# SCH_Reserach-project_2025-06-22.net
KiCad netlist of a schematic drawn in EasyEDA
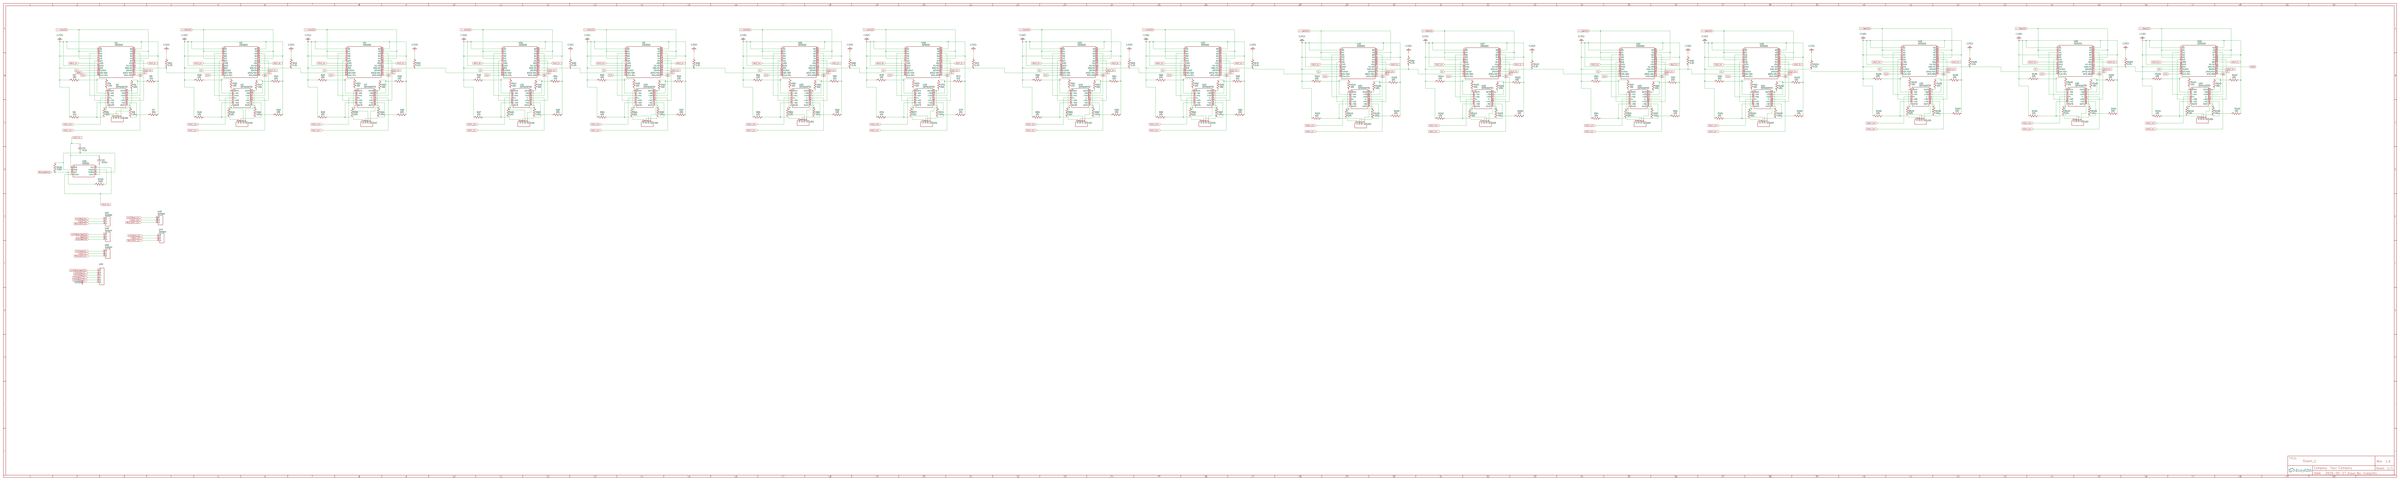
[diagram p0: Sheet_1]
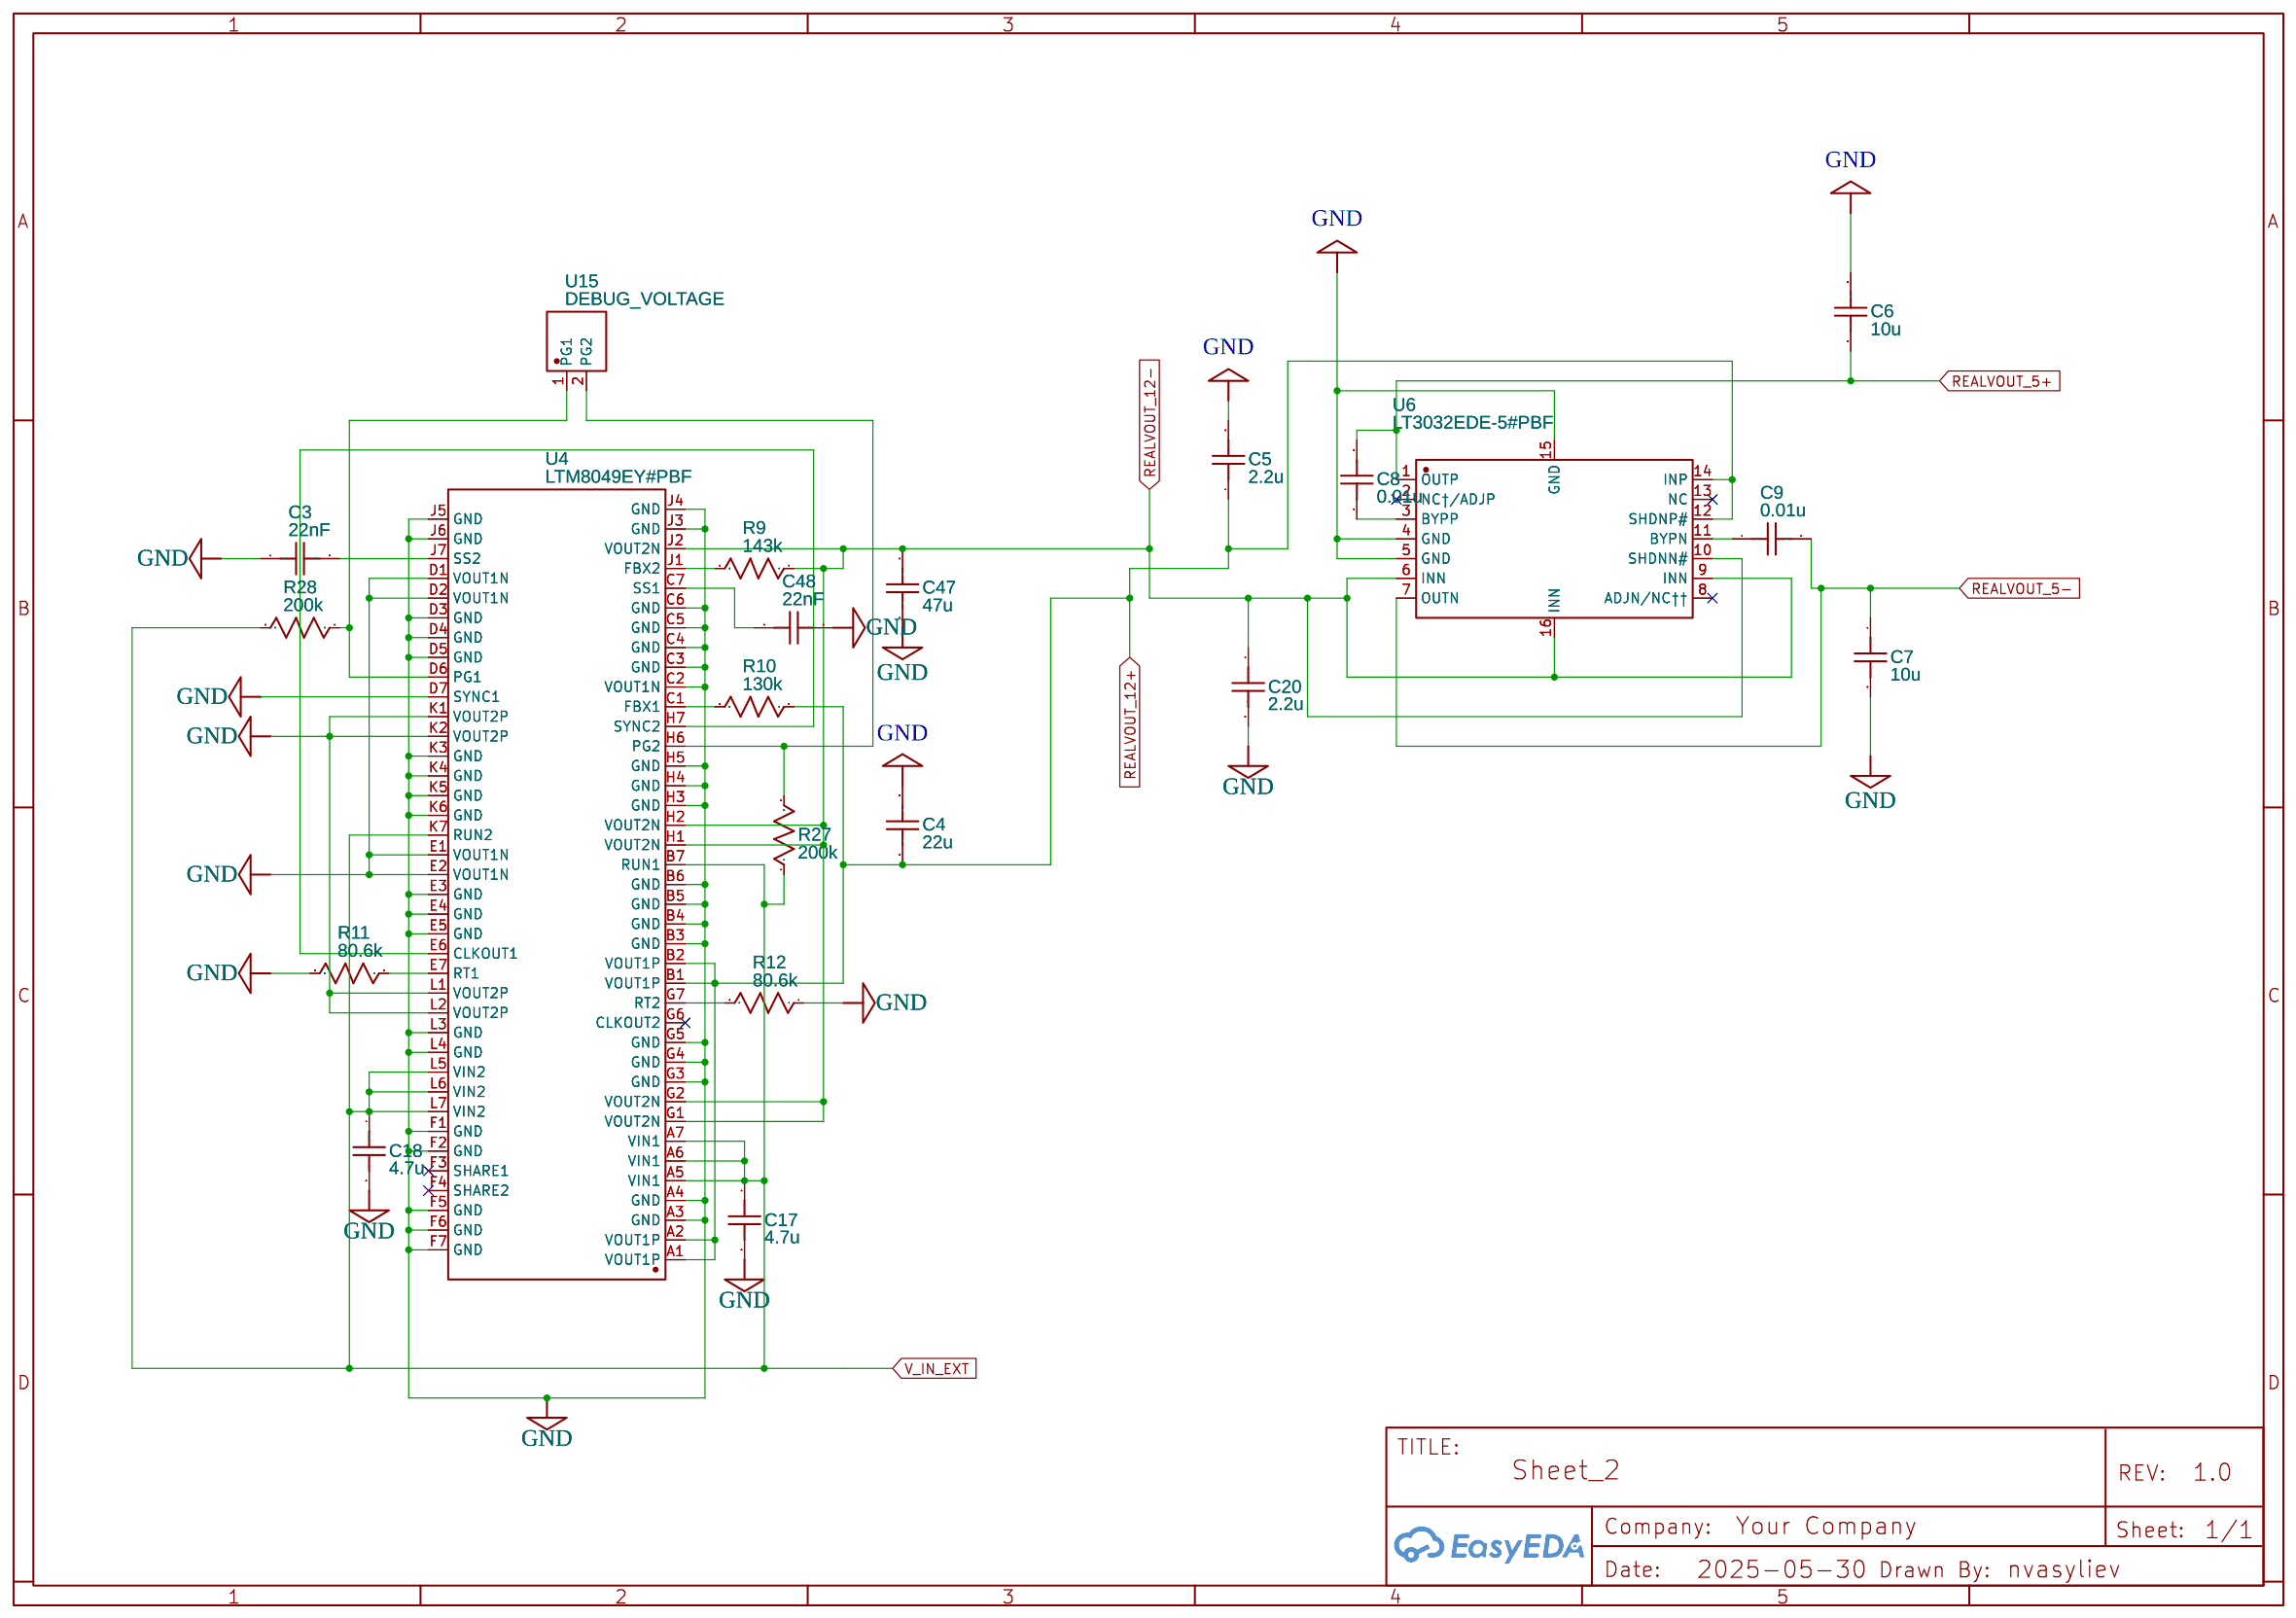
[diagram p1: Sheet_2]
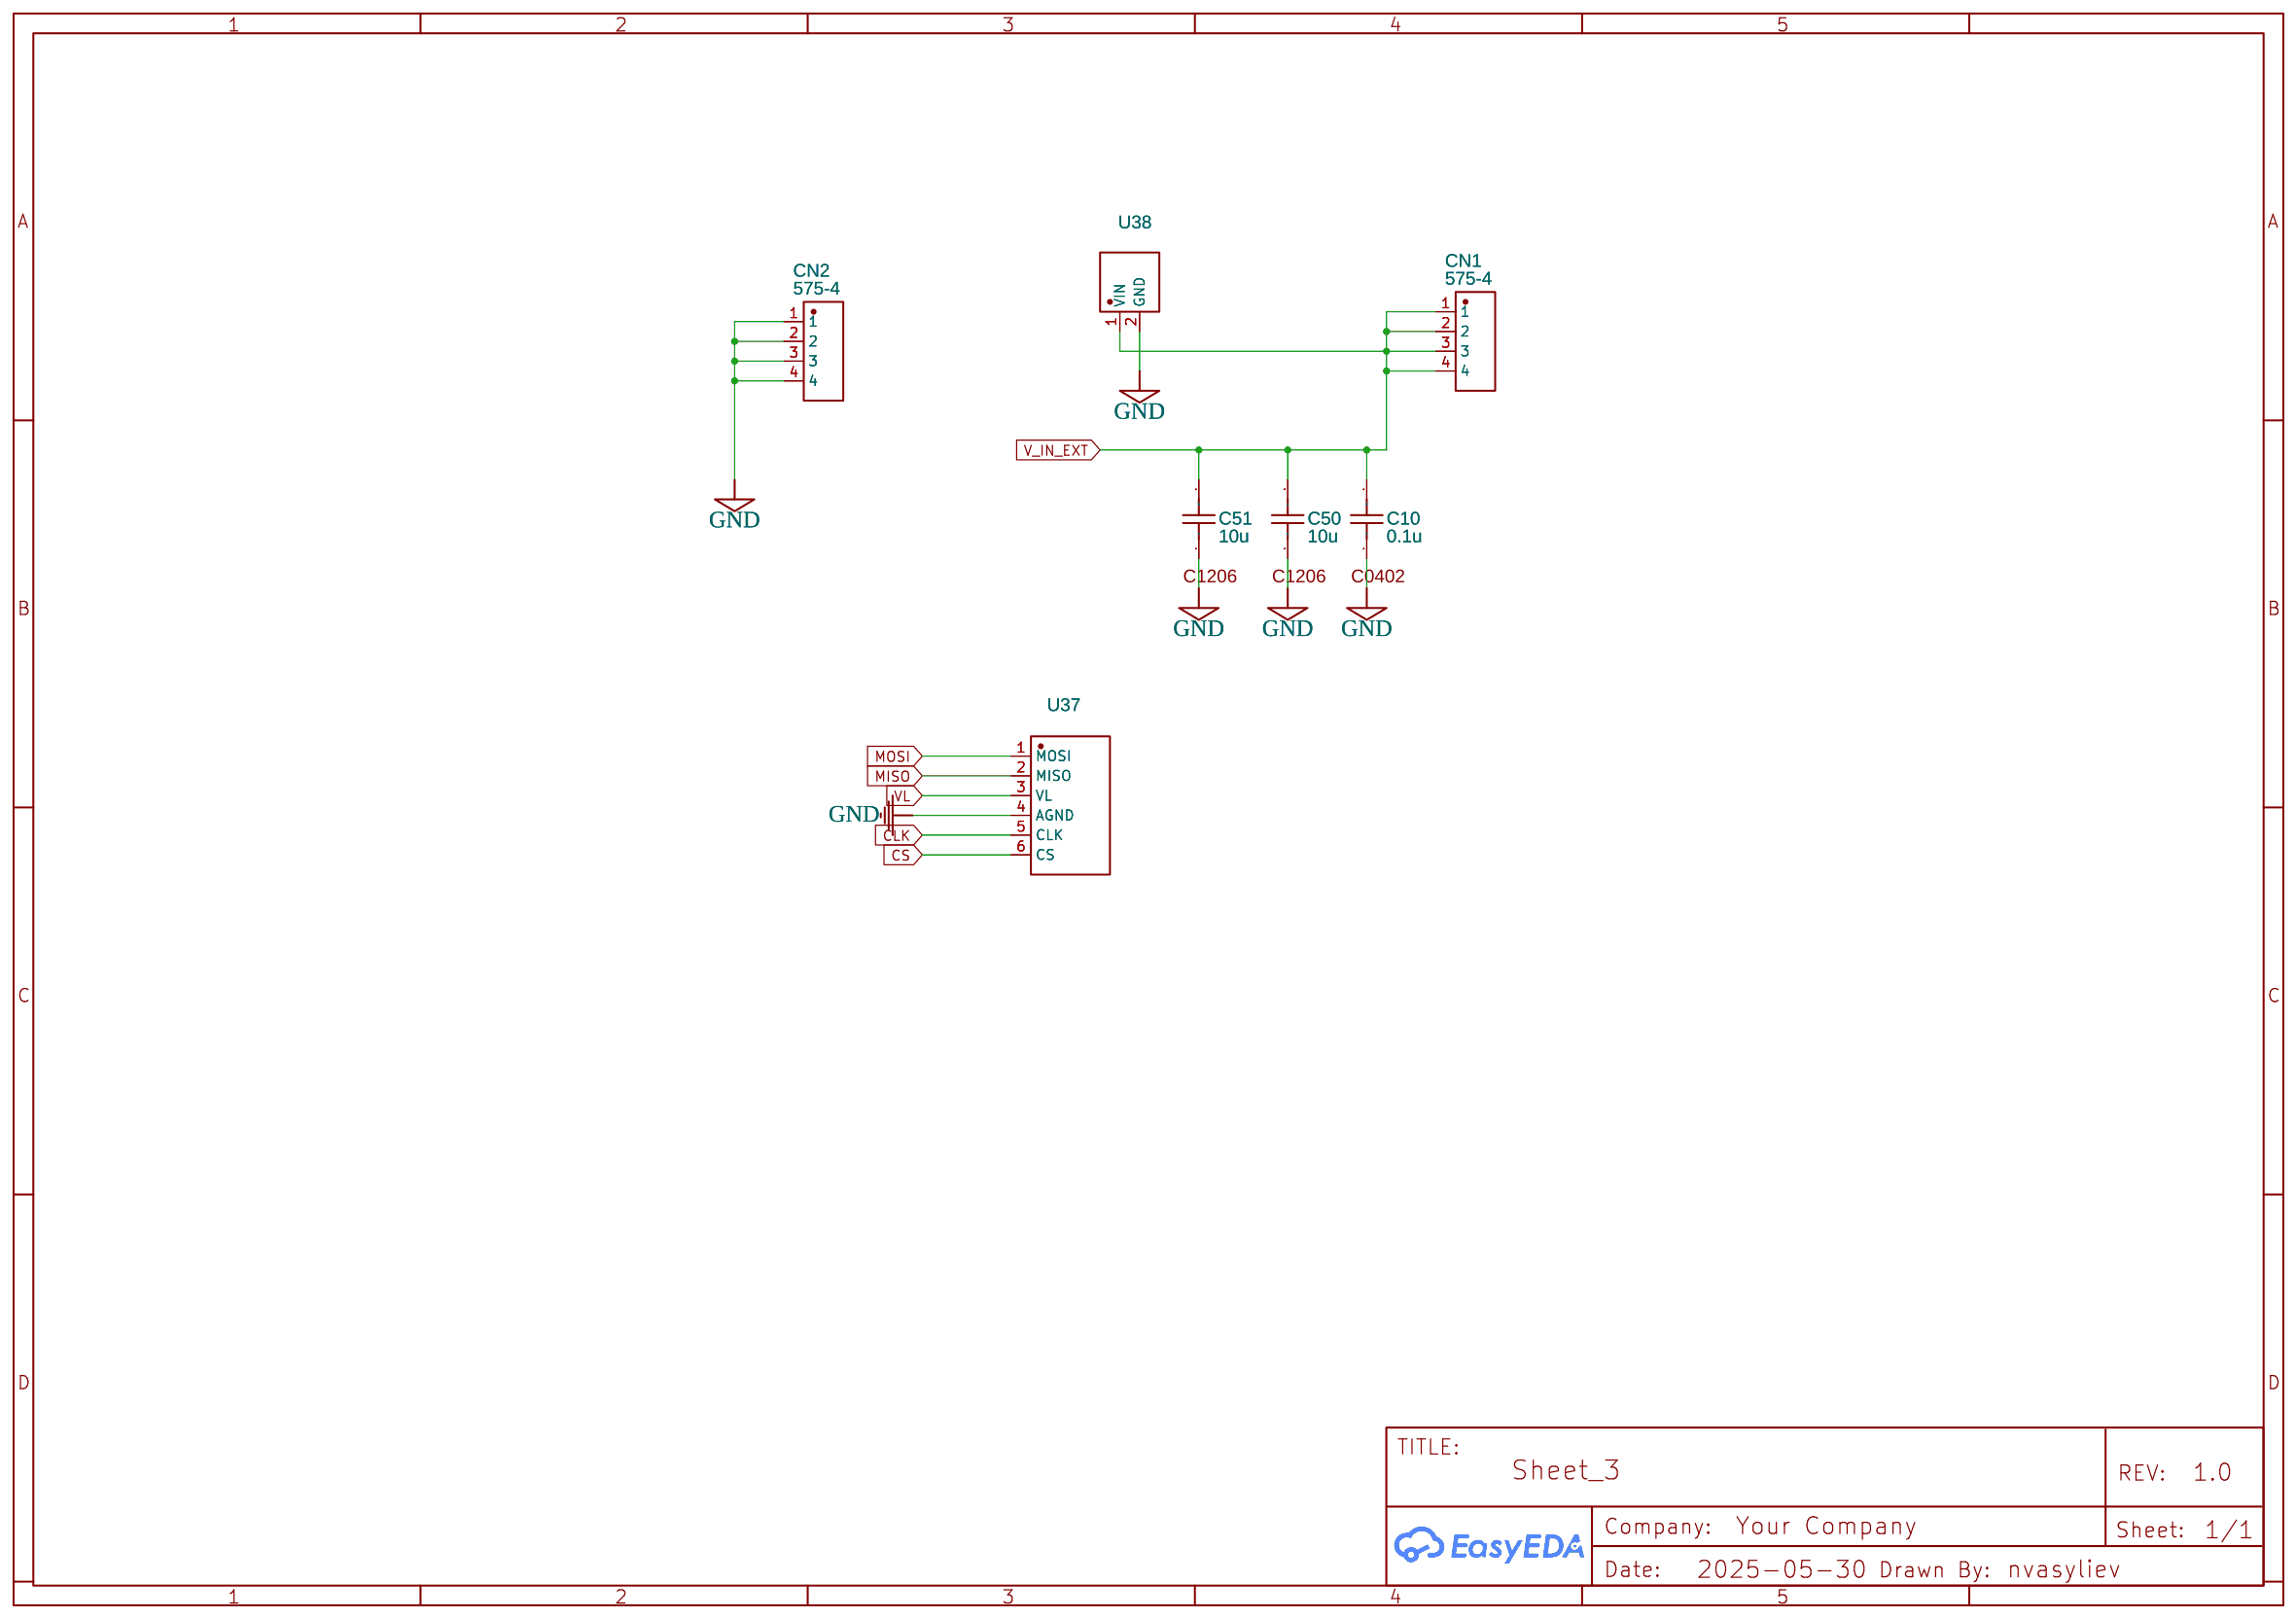
[diagram p2: Sheet_3]

(export (version "E")
  (design (tool "Eeschema 10.0.6"))
  (components
    (comp (ref "C1") (value "0.1u") (libsource (lib "") (part "C_0603_US")))
    (comp (ref "C2") (value "0.01u") (libsource (lib "") (part "C_0603_US")))
    (comp (ref "R1") (value "10k") (libsource (lib "") (part "R_0603_US")))
    (comp (ref "R2") (value "10k") (libsource (lib "") (part "R_0603_US_1")))
    (comp (ref "R3") (value "10k") (libsource (lib "") (part "R_0603_US")))
    (comp (ref "R4") (value "10k") (libsource (lib "") (part "R_0603_US_1")))
    (comp (ref "R5") (value "10k") (libsource (lib "") (part "R_0603_US")))
    (comp (ref "R6") (value "10k") (libsource (lib "") (part "R_0603_US")))
    (comp (ref "R7") (value "10k") (libsource (lib "") (part "R_0603_US_1")))
    (comp (ref "R8") (value "10k") (libsource (lib "") (part "R_0603_US_1")))
    (comp (ref "R13") (value "2.2k") (libsource (lib "") (part "R_0603_US")))
    (comp (ref "R14") (value "10k") (libsource (lib "") (part "R_0603_US_1")))
    (comp (ref "R15") (value "10k") (libsource (lib "") (part "R_0603_US_1")))
    (comp (ref "R16") (value "10k") (libsource (lib "") (part "R_0603_US")))
    (comp (ref "R17") (value "10k") (libsource (lib "") (part "R_0603_US")))
    (comp (ref "R18") (value "10k") (libsource (lib "") (part "R_0603_US_1")))
    (comp (ref "R19") (value "10k") (libsource (lib "") (part "R_0603_US")))
    (comp (ref "R20") (value "10k") (libsource (lib "") (part "R_0603_US_1")))
    (comp (ref "R21") (value "2.2k") (libsource (lib "") (part "R_0603_US")))
    (comp (ref "R22") (value "10k") (libsource (lib "") (part "R_0603_US")))
    (comp (ref "R23") (value "10k") (libsource (lib "") (part "R_0603_US")))
    (comp (ref "R24") (value "10k") (libsource (lib "") (part "R_0603_US_1")))
    (comp (ref "R25") (value "10k") (libsource (lib "") (part "R_0603_US")))
    (comp (ref "R26") (value "2.2k") (libsource (lib "") (part "R_0603_US")))
    (comp (ref "R29") (value "10k") (libsource (lib "") (part "R_0603_US_1")))
    (comp (ref "R30") (value "10k") (libsource (lib "") (part "R_0603_US")))
    (comp (ref "R31") (value "10k") (libsource (lib "") (part "R_0603_US")))
    (comp (ref "R32") (value "10k") (libsource (lib "") (part "R_0603_US_1")))
    (comp (ref "R33") (value "10k") (libsource (lib "") (part "R_0603_US_1")))
    (comp (ref "R34") (value "2.2k") (libsource (lib "") (part "R_0603_US")))
    (comp (ref "R35") (value "2.2k") (libsource (lib "") (part "R_0603_US")))
    (comp (ref "R36") (value "10k") (libsource (lib "") (part "R_0603_US_1")))
    (comp (ref "R37") (value "10k") (libsource (lib "") (part "R_0603_US_1")))
    (comp (ref "R38") (value "10k") (libsource (lib "") (part "R_0603_US")))
    (comp (ref "R39") (value "10k") (libsource (lib "") (part "R_0603_US")))
    (comp (ref "R40") (value "10k") (libsource (lib "") (part "R_0603_US_1")))
    (comp (ref "R41") (value "10k") (libsource (lib "") (part "R_0603_US")))
    (comp (ref "R42") (value "10k") (libsource (lib "") (part "R_0603_US_1")))
    (comp (ref "R43") (value "10k") (libsource (lib "") (part "R_0603_US")))
    (comp (ref "R44") (value "10k") (libsource (lib "") (part "R_0603_US")))
    (comp (ref "R45") (value "10k") (libsource (lib "") (part "R_0603_US_1")))
    (comp (ref "R46") (value "10k") (libsource (lib "") (part "R_0603_US")))
    (comp (ref "R47") (value "10k") (libsource (lib "") (part "R_0603_US_1")))
    (comp (ref "R48") (value "10k") (libsource (lib "") (part "R_0603_US")))
    (comp (ref "R49") (value "10k") (libsource (lib "") (part "R_0603_US")))
    (comp (ref "R50") (value "10k") (libsource (lib "") (part "R_0603_US_1")))
    (comp (ref "R51") (value "10k") (libsource (lib "") (part "R_0603_US_1")))
    (comp (ref "R52") (value "2.2k") (libsource (lib "") (part "R_0603_US")))
    (comp (ref "R53") (value "2.2k") (libsource (lib "") (part "R_0603_US")))
    (comp (ref "R54") (value "10k") (libsource (lib "") (part "R_0603_US_1")))
    (comp (ref "R55") (value "10k") (libsource (lib "") (part "R_0603_US_1")))
    (comp (ref "R56") (value "10k") (libsource (lib "") (part "R_0603_US")))
    (comp (ref "R57") (value "10k") (libsource (lib "") (part "R_0603_US")))
    (comp (ref "R58") (value "10k") (libsource (lib "") (part "R_0603_US_1")))
    (comp (ref "R59") (value "10k") (libsource (lib "") (part "R_0603_US")))
    (comp (ref "R60") (value "10k") (libsource (lib "") (part "R_0603_US_1")))
    (comp (ref "R61") (value "10k") (libsource (lib "") (part "R_0603_US")))
    (comp (ref "R62") (value "10k") (libsource (lib "") (part "R_0603_US")))
    (comp (ref "R63") (value "10k") (libsource (lib "") (part "R_0603_US_1")))
    (comp (ref "R64") (value "10k") (libsource (lib "") (part "R_0603_US")))
    (comp (ref "R65") (value "10k") (libsource (lib "") (part "R_0603_US_1")))
    (comp (ref "R66") (value "10k") (libsource (lib "") (part "R_0603_US")))
    (comp (ref "R67") (value "10k") (libsource (lib "") (part "R_0603_US")))
    (comp (ref "R68") (value "10k") (libsource (lib "") (part "R_0603_US_1")))
    (comp (ref "R69") (value "10k") (libsource (lib "") (part "R_0603_US_1")))
    (comp (ref "R70") (value "2.2k") (libsource (lib "") (part "R_0603_US")))
    (comp (ref "R71") (value "2.2k") (libsource (lib "") (part "R_0603_US")))
    (comp (ref "R72") (value "10k") (libsource (lib "") (part "R_0603_US_1")))
    (comp (ref "R73") (value "10k") (libsource (lib "") (part "R_0603_US_1")))
    (comp (ref "R74") (value "10k") (libsource (lib "") (part "R_0603_US")))
    (comp (ref "R75") (value "10k") (libsource (lib "") (part "R_0603_US")))
    (comp (ref "R76") (value "10k") (libsource (lib "") (part "R_0603_US_1")))
    (comp (ref "R77") (value "10k") (libsource (lib "") (part "R_0603_US")))
    (comp (ref "R78") (value "10k") (libsource (lib "") (part "R_0603_US_1")))
    (comp (ref "R79") (value "10k") (libsource (lib "") (part "R_0603_US")))
    (comp (ref "R80") (value "10k") (libsource (lib "") (part "R_0603_US")))
    (comp (ref "R81") (value "10k") (libsource (lib "") (part "R_0603_US_1")))
    (comp (ref "R82") (value "10k") (libsource (lib "") (part "R_0603_US")))
    (comp (ref "R83") (value "10k") (libsource (lib "") (part "R_0603_US_1")))
    (comp (ref "R84") (value "10k") (libsource (lib "") (part "R_0603_US")))
    (comp (ref "R85") (value "10k") (libsource (lib "") (part "R_0603_US")))
    (comp (ref "R86") (value "10k") (libsource (lib "") (part "R_0603_US_1")))
    (comp (ref "R87") (value "10k") (libsource (lib "") (part "R_0603_US_1")))
    (comp (ref "R88") (value "2.2k") (libsource (lib "") (part "R_0603_US")))
    (comp (ref "R89") (value "2.2k") (libsource (lib "") (part "R_0603_US")))
    (comp (ref "R90") (value "10k") (libsource (lib "") (part "R_0603_US_1")))
    (comp (ref "R91") (value "10k") (libsource (lib "") (part "R_0603_US_1")))
    (comp (ref "R92") (value "10k") (libsource (lib "") (part "R_0603_US")))
    (comp (ref "R93") (value "10k") (libsource (lib "") (part "R_0603_US")))
    (comp (ref "R94") (value "10k") (libsource (lib "") (part "R_0603_US_1")))
    (comp (ref "R95") (value "10k") (libsource (lib "") (part "R_0603_US")))
    (comp (ref "R96") (value "10k") (libsource (lib "") (part "R_0603_US_1")))
    (comp (ref "R97") (value "10k") (libsource (lib "") (part "R_0603_US")))
    (comp (ref "R98") (value "10k") (libsource (lib "") (part "R_0603_US")))
    (comp (ref "R99") (value "10k") (libsource (lib "") (part "R_0603_US_1")))
    (comp (ref "R100") (value "10k") (libsource (lib "") (part "R_0603_US")))
    (comp (ref "R101") (value "10k") (libsource (lib "") (part "R_0603_US_1")))
    (comp (ref "R102") (value "10k") (libsource (lib "") (part "R_0603_US")))
    (comp (ref "R103") (value "10k") (libsource (lib "") (part "R_0603_US")))
    (comp (ref "R104") (value "10k") (libsource (lib "") (part "R_0603_US_1")))
    (comp (ref "R105") (value "10k") (libsource (lib "") (part "R_0603_US_1")))
    (comp (ref "R106") (value "2.2k") (libsource (lib "") (part "R_0603_US")))
    (comp (ref "R107") (value "2.2k") (libsource (lib "") (part "R_0603_US")))
    (comp (ref "R108") (value "10k") (libsource (lib "") (part "R_0603_US_1")))
    (comp (ref "R109") (value "10k") (libsource (lib "") (part "R_0603_US_1")))
    (comp (ref "R110") (value "10k") (libsource (lib "") (part "R_0603_US")))
    (comp (ref "R111") (value "10k") (libsource (lib "") (part "R_0603_US")))
    (comp (ref "R112") (value "10k") (libsource (lib "") (part "R_0603_US_1")))
    (comp (ref "R113") (value "10k") (libsource (lib "") (part "R_0603_US")))
    (comp (ref "R114") (value "10k") (libsource (lib "") (part "R_0603_US_1")))
    (comp (ref "R115") (value "10k") (libsource (lib "") (part "R_0603_US")))
    (comp (ref "R116") (value "10k") (libsource (lib "") (part "R_0603_US")))
    (comp (ref "R117") (value "10k") (libsource (lib "") (part "R_0603_US_1")))
    (comp (ref "R118") (value "10k") (libsource (lib "") (part "R_0603_US")))
    (comp (ref "R119") (value "10k") (libsource (lib "") (part "R_0603_US_1")))
    (comp (ref "R120") (value "10k") (libsource (lib "") (part "R_0603_US")))
    (comp (ref "R121") (value "10k") (libsource (lib "") (part "R_0603_US")))
    (comp (ref "R122") (value "10k") (libsource (lib "") (part "R_0603_US_1")))
    (comp (ref "R123") (value "10k") (libsource (lib "") (part "R_0603_US_1")))
    (comp (ref "R125") (value "10k") (libsource (lib "") (part "R_0603_US")))
    (comp (ref "R126") (value "10k") (libsource (lib "") (part "R_0603_US_1")))
    (comp (ref "R127") (value "10k") (libsource (lib "") (part "R_0603_US")))
    (comp (ref "R128") (value "10k") (libsource (lib "") (part "R_0603_US_1")))
    (comp (ref "R129") (value "7150") (libsource (lib "") (part "R_0603_US_1")))
    (comp (ref "R130") (value "7150") (libsource (lib "") (part "R_0603_US")))
    (comp (ref "R131") (value "10k") (libsource (lib "") (part "R_0603_US")))
    (comp (ref "R132") (value "10k") (libsource (lib "") (part "R_0603_US")))
    (comp (ref "R133") (value "10k") (libsource (lib "") (part "R_0603_US_1")))
    (comp (ref "R134") (value "10k") (libsource (lib "") (part "R_0603_US_1")))
    (comp (ref "R135") (value "2.2k") (libsource (lib "") (part "R_0603_US")))
    (comp (ref "R137") (value "10k") (libsource (lib "") (part "R_0603_US_1")))
    (comp (ref "R138") (value "10k") (libsource (lib "") (part "R_0603_US_1")))
    (comp (ref "R139") (value "10k") (libsource (lib "") (part "R_0603_US")))
    (comp (ref "R140") (value "10k") (libsource (lib "") (part "R_0603_US")))
    (comp (ref "R141") (value "10k") (libsource (lib "") (part "R_0603_US_1")))
    (comp (ref "R142") (value "10k") (libsource (lib "") (part "R_0603_US")))
    (comp (ref "R143") (value "10k") (libsource (lib "") (part "R_0603_US_1")))
    (comp (ref "R144") (value "10k") (libsource (lib "") (part "R_0603_US")))
    (comp (ref "R145") (value "10k") (libsource (lib "") (part "R_0603_US")))
    (comp (ref "R146") (value "10k") (libsource (lib "") (part "R_0603_US_1")))
    (comp (ref "R147") (value "10k") (libsource (lib "") (part "R_0603_US")))
    (comp (ref "R148") (value "10k") (libsource (lib "") (part "R_0603_US_1")))
    (comp (ref "R149") (value "10k") (libsource (lib "") (part "R_0603_US")))
    (comp (ref "R150") (value "10k") (libsource (lib "") (part "R_0603_US")))
    (comp (ref "R151") (value "10k") (libsource (lib "") (part "R_0603_US_1")))
    (comp (ref "R152") (value "10k") (libsource (lib "") (part "R_0603_US_1")))
    (comp (ref "R153") (value "2.2k") (libsource (lib "") (part "R_0603_US")))
    (comp (ref "U1")
      (value "AD5263")
      (fields (field (name "Manufacturer Part") "AD5263BRUZ20") (field (name "Manufacturer") "ADI(亚德诺)"))
      (libsource (lib "") (part "AD5263BRUZ20"))
    )
    (comp (ref "U2")
      (value "OPA4197ID")
      (fields (field (name "Manufacturer") "TI(德州仪器)"))
      (libsource (lib "") (part "OPA4197ID"))
    )
    (comp (ref "U3")
      (value "AD5263")
      (fields (field (name "Manufacturer Part") "AD5263BRUZ20") (field (name "Manufacturer") "ADI(亚德诺)"))
      (libsource (lib "") (part "AD5263BRUZ20"))
    )
    (comp (ref "U5")
      (value "OPA4197ID")
      (fields (field (name "Manufacturer") "TI(德州仪器)"))
      (libsource (lib "") (part "OPA4197ID"))
    )
    (comp (ref "U7")
      (value "OPA4197ID")
      (fields (field (name "Manufacturer") "TI(德州仪器)"))
      (libsource (lib "") (part "OPA4197ID"))
    )
    (comp (ref "U8")
      (value "AD5263")
      (fields (field (name "Manufacturer Part") "AD5263BRUZ20") (field (name "Manufacturer") "ADI(亚德诺)"))
      (libsource (lib "") (part "AD5263BRUZ20"))
    )
    (comp (ref "U9")
      (value "AD5263")
      (fields (field (name "Manufacturer Part") "AD5263BRUZ20") (field (name "Manufacturer") "ADI(亚德诺)"))
      (libsource (lib "") (part "AD5263BRUZ20"))
    )
    (comp (ref "U10")
      (value "OPA4197ID")
      (fields (field (name "Manufacturer") "TI(德州仪器)"))
      (libsource (lib "") (part "OPA4197ID"))
    )
    (comp (ref "U11")
      (value "OPA4197ID")
      (fields (field (name "Manufacturer") "TI(德州仪器)"))
      (libsource (lib "") (part "OPA4197ID"))
    )
    (comp (ref "U12")
      (value "AD5263")
      (fields (field (name "Manufacturer Part") "AD5263BRUZ20") (field (name "Manufacturer") "ADI(亚德诺)"))
      (libsource (lib "") (part "AD5263BRUZ20"))
    )
    (comp (ref "U13")
      (value "AD5263")
      (fields (field (name "Manufacturer Part") "AD5263BRUZ20") (field (name "Manufacturer") "ADI(亚德诺)"))
      (libsource (lib "") (part "AD5263BRUZ20"))
    )
    (comp (ref "U14")
      (value "OPA4197ID")
      (fields (field (name "Manufacturer") "TI(德州仪器)"))
      (libsource (lib "") (part "OPA4197ID"))
    )
    (comp (ref "U16")
      (value "OPA4197ID")
      (fields (field (name "Manufacturer") "TI(德州仪器)"))
      (libsource (lib "") (part "OPA4197ID"))
    )
    (comp (ref "U17")
      (value "AD5263")
      (fields (field (name "Manufacturer Part") "AD5263BRUZ20") (field (name "Manufacturer") "ADI(亚德诺)"))
      (libsource (lib "") (part "AD5263BRUZ20"))
    )
    (comp (ref "U18")
      (value "AD5263")
      (fields (field (name "Manufacturer Part") "AD5263BRUZ20") (field (name "Manufacturer") "ADI(亚德诺)"))
      (libsource (lib "") (part "AD5263BRUZ20"))
    )
    (comp (ref "U19")
      (value "OPA4197ID")
      (fields (field (name "Manufacturer") "TI(德州仪器)"))
      (libsource (lib "") (part "OPA4197ID"))
    )
    (comp (ref "U20")
      (value "OPA4197ID")
      (fields (field (name "Manufacturer") "TI(德州仪器)"))
      (libsource (lib "") (part "OPA4197ID"))
    )
    (comp (ref "U21")
      (value "AD5263")
      (fields (field (name "Manufacturer Part") "AD5263BRUZ20") (field (name "Manufacturer") "ADI(亚德诺)"))
      (libsource (lib "") (part "AD5263BRUZ20"))
    )
    (comp (ref "U22")
      (value "AD5263")
      (fields (field (name "Manufacturer Part") "AD5263BRUZ20") (field (name "Manufacturer") "ADI(亚德诺)"))
      (libsource (lib "") (part "AD5263BRUZ20"))
    )
    (comp (ref "U23")
      (value "OPA4197ID")
      (fields (field (name "Manufacturer") "TI(德州仪器)"))
      (libsource (lib "") (part "OPA4197ID"))
    )
    (comp (ref "U24")
      (value "OPA4197ID")
      (fields (field (name "Manufacturer") "TI(德州仪器)"))
      (libsource (lib "") (part "OPA4197ID"))
    )
    (comp (ref "U25") (value "NE555") (libsource (lib "") (part "NE555")))
    (comp (ref "U26")
      (value "AD5263")
      (fields (field (name "Manufacturer Part") "AD5263BRUZ20") (field (name "Manufacturer") "ADI(亚德诺)"))
      (libsource (lib "") (part "AD5263BRUZ20"))
    )
    (comp (ref "U27")
      (value "AD5263")
      (fields (field (name "Manufacturer Part") "AD5263BRUZ20") (field (name "Manufacturer") "ADI(亚德诺)"))
      (libsource (lib "") (part "AD5263BRUZ20"))
    )
    (comp (ref "U28")
      (value "OPA4197ID")
      (fields (field (name "Manufacturer") "TI(德州仪器)"))
      (libsource (lib "") (part "OPA4197ID"))
    )
    (comp (ref "U29")
      (value "OPA4197ID")
      (fields (field (name "Manufacturer") "TI(德州仪器)"))
      (libsource (lib "") (part "OPA4197ID"))
    )
    (comp (ref "U30")
      (value "AD5263")
      (fields (field (name "Manufacturer Part") "AD5263BRUZ20") (field (name "Manufacturer") "ADI(亚德诺)"))
      (libsource (lib "") (part "AD5263BRUZ20"))
    )
    (comp (ref "U31")
      (value "OPA4197ID")
      (fields (field (name "Manufacturer") "TI(德州仪器)"))
      (libsource (lib "") (part "OPA4197ID"))
    )
    (comp (ref "U32")
      (value "AD5263")
      (fields (field (name "Manufacturer Part") "AD5263BRUZ20") (field (name "Manufacturer") "ADI(亚德诺)"))
      (libsource (lib "") (part "AD5263BRUZ20"))
    )
    (comp (ref "U33")
      (value "AD5263")
      (fields (field (name "Manufacturer Part") "AD5263BRUZ20") (field (name "Manufacturer") "ADI(亚德诺)"))
      (libsource (lib "") (part "AD5263BRUZ20"))
    )
    (comp (ref "U34")
      (value "OPA4197ID")
      (fields (field (name "Manufacturer") "TI(德州仪器)"))
      (libsource (lib "") (part "OPA4197ID"))
    )
    (comp (ref "U35")
      (value "OPA4197ID")
      (fields (field (name "Manufacturer") "TI(德州仪器)"))
      (libsource (lib "") (part "OPA4197ID"))
    )
    (comp (ref "U36")
      (value "AD5263")
      (fields (field (name "Manufacturer Part") "AD5263BRUZ20") (field (name "Manufacturer") "ADI(亚德诺)"))
      (libsource (lib "") (part "AD5263BRUZ20"))
    )
    (comp (ref "U39") (value "NO") (libsource (lib "") (part "Unknown_280_-1580")))
    (comp (ref "U40") (value "Jumper") (libsource (lib "") (part "Unknown_240_-1090")))
    (comp (ref "U41") (value "Jumper") (libsource (lib "") (part "Unknown_240_-1155")))
    (comp (ref "U42") (value "Jumper") (libsource (lib "") (part "Unknown_240_-1020")))
    (comp (ref "U43") (value "Jumper") (libsource (lib "") (part "Unknown_460_-1160")))
    (comp (ref "U44") (value "Jumper") (libsource (lib "") (part "Unknown_465_-1085")))
    (comp (ref "U45") (value "NO") (libsource (lib "") (part "Unknown_215_-925")))
    (comp (ref "U46") (value "NO") (libsource (lib "") (part "Unknown_800_-1560")))
    (comp (ref "U47") (value "NO") (libsource (lib "") (part "Unknown_1320_-1560")))
    (comp (ref "U48") (value "NO") (libsource (lib "") (part "Unknown_1975_-1560")))
    (comp (ref "U49") (value "NO") (libsource (lib "") (part "Unknown_2490_-1560")))
    (comp (ref "U50") (value "NO") (libsource (lib "") (part "Unknown_3140_-1565")))
    (comp (ref "U51") (value "NO") (libsource (lib "") (part "Unknown_3655_-1560")))
    (comp (ref "U52") (value "NO") (libsource (lib "") (part "Unknown_4300_-1560")))
    (comp (ref "U53") (value "NO") (libsource (lib "") (part "Unknown_4815_-1560")))
    (comp (ref "U54") (value "NO") (libsource (lib "") (part "Unknown_5465_-1555")))
    (comp (ref "U55") (value "NO") (libsource (lib "") (part "Unknown_5985_-1560")))
    (comp (ref "U56") (value "NO") (libsource (lib "") (part "Unknown_6630_-1560")))
    (comp (ref "U57") (value "NO") (libsource (lib "") (part "Unknown_7145_-1560")))
    (comp (ref "U58") (value "NO") (libsource (lib "") (part "Unknown_7800_-1570")))
    (comp (ref "U59") (value "NO") (libsource (lib "") (part "Unknown_8455_-1565")))
    (comp (ref "U60") (value "NO") (libsource (lib "") (part "Unknown_8975_-1575")))
    (comp (ref "C3") (value "22nF") (libsource (lib "") (part "C_1206_US")))
    (comp (ref "C4") (value "22u") (libsource (lib "") (part "C_1206_US_1")))
    (comp (ref "C5") (value "2.2u") (libsource (lib "") (part "C_0603_US_2")))
    (comp (ref "C6") (value "10u") (libsource (lib "") (part "C_0603_US_2")))
    (comp (ref "C7") (value "10u") (libsource (lib "") (part "C_0603_US_1")))
    (comp (ref "C8") (value "0.01u") (libsource (lib "") (part "C_0603_US_2")))
    (comp (ref "C9") (value "0.01u") (libsource (lib "") (part "C_0603_US")))
    (comp (ref "C17") (value "4.7u") (libsource (lib "") (part "C_0603_US_1")))
    (comp (ref "C18") (value "4.7u") (libsource (lib "") (part "C_0603_US_1")))
    (comp (ref "C20") (value "2.2u") (libsource (lib "") (part "C_0603_US_1")))
    (comp (ref "C47") (value "47u") (libsource (lib "") (part "C_1206_US_1")))
    (comp (ref "C48") (value "22nF") (libsource (lib "") (part "C_1206_US")))
    (comp (ref "R9") (value "143k") (libsource (lib "") (part "R_0603_US_1")))
    (comp (ref "R10") (value "130k") (libsource (lib "") (part "R_0603_US_1")))
    (comp (ref "R11") (value "80.6k") (libsource (lib "") (part "R_0603_US_1")))
    (comp (ref "R12") (value "80.6k") (libsource (lib "") (part "R_0603_US_1")))
    (comp (ref "R27") (value "200k") (libsource (lib "") (part "R_0603_US")))
    (comp (ref "R28") (value "200k") (libsource (lib "") (part "R_0603_US_1")))
    (comp (ref "U4")
      (value "LTM8049EY#PBF")
      (fields (field (name "Manufacturer") "ADI(亚德诺)"))
      (libsource (lib "") (part "LTM8049EY#PBF"))
    )
    (comp (ref "U6")
      (value "LT3032EDE-5#PBF")
      (fields (field (name "Manufacturer") "ADI(亚德诺)"))
      (libsource (lib "") (part "LT3032EDE-5#PBF"))
    )
    (comp (ref "U15") (value "DEBUG_VOLTAGE") (libsource (lib "") (part "DEBUG_VOLTAGE")))
    (comp (ref "C10") (value "0.1u") (libsource (lib "") (part "C_0603_US_1")))
    (comp (ref "C50") (value "10u") (libsource (lib "") (part "C_0603_US")))
    (comp (ref "C51") (value "10u") (libsource (lib "") (part "C_0603_US")))
    (comp (ref "CN1")
      (value "575-4")
      (fields (field (name "Manufacturer") "Keystone"))
      (libsource (lib "") (part "575-4"))
    )
    (comp (ref "CN2")
      (value "575-4")
      (fields (field (name "Manufacturer") "Keystone"))
      (libsource (lib "") (part "575-4"))
    )
    (comp (ref "U37") (value "~") (libsource (lib "") (part "Unknown_535_-405")))
    (comp (ref "U38") (value "~") (libsource (lib "") (part "Unknown_565_-670")))
  )
  (nets
    (net (code "1") (name "+-5WAVES") (class "Default")
      (node (ref "U1") (pin "2") (pinfunction "A1_2") (pintype "unspecified"))
      (node (ref "U1") (pin "20") (pinfunction "A4_20") (pintype "unspecified"))
      (node (ref "U1") (pin "23") (pinfunction "A2_23") (pintype "unspecified"))
      (node (ref "U1") (pin "5") (pinfunction "A3_5") (pintype "unspecified"))
      (node (ref "U12") (pin "2") (pinfunction "A1_2") (pintype "unspecified"))
      (node (ref "U12") (pin "20") (pinfunction "A4_20") (pintype "unspecified"))
      (node (ref "U12") (pin "23") (pinfunction "A2_23") (pintype "unspecified"))
      (node (ref "U12") (pin "5") (pinfunction "A3_5") (pintype "unspecified"))
      (node (ref "U13") (pin "2") (pinfunction "A1_2") (pintype "unspecified"))
      (node (ref "U13") (pin "20") (pinfunction "A4_20") (pintype "unspecified"))
      (node (ref "U13") (pin "23") (pinfunction "A2_23") (pintype "unspecified"))
      (node (ref "U13") (pin "5") (pinfunction "A3_5") (pintype "unspecified"))
      (node (ref "U17") (pin "2") (pinfunction "A1_2") (pintype "unspecified"))
      (node (ref "U17") (pin "20") (pinfunction "A4_20") (pintype "unspecified"))
      (node (ref "U17") (pin "23") (pinfunction "A2_23") (pintype "unspecified"))
      (node (ref "U17") (pin "5") (pinfunction "A3_5") (pintype "unspecified"))
      (node (ref "U18") (pin "2") (pinfunction "A1_2") (pintype "unspecified"))
      (node (ref "U18") (pin "20") (pinfunction "A4_20") (pintype "unspecified"))
      (node (ref "U18") (pin "23") (pinfunction "A2_23") (pintype "unspecified"))
      (node (ref "U18") (pin "5") (pinfunction "A3_5") (pintype "unspecified"))
      (node (ref "U21") (pin "2") (pinfunction "A1_2") (pintype "unspecified"))
      (node (ref "U21") (pin "20") (pinfunction "A4_20") (pintype "unspecified"))
      (node (ref "U21") (pin "23") (pinfunction "A2_23") (pintype "unspecified"))
      (node (ref "U21") (pin "5") (pinfunction "A3_5") (pintype "unspecified"))
      (node (ref "U22") (pin "2") (pinfunction "A1_2") (pintype "unspecified"))
      (node (ref "U22") (pin "20") (pinfunction "A4_20") (pintype "unspecified"))
      (node (ref "U22") (pin "23") (pinfunction "A2_23") (pintype "unspecified"))
      (node (ref "U22") (pin "5") (pinfunction "A3_5") (pintype "unspecified"))
      (node (ref "U26") (pin "2") (pinfunction "A1_2") (pintype "unspecified"))
      (node (ref "U26") (pin "20") (pinfunction "A4_20") (pintype "unspecified"))
      (node (ref "U26") (pin "23") (pinfunction "A2_23") (pintype "unspecified"))
      (node (ref "U26") (pin "5") (pinfunction "A3_5") (pintype "unspecified"))
      (node (ref "U27") (pin "2") (pinfunction "A1_2") (pintype "unspecified"))
      (node (ref "U27") (pin "20") (pinfunction "A4_20") (pintype "unspecified"))
      (node (ref "U27") (pin "23") (pinfunction "A2_23") (pintype "unspecified"))
      (node (ref "U27") (pin "5") (pinfunction "A3_5") (pintype "unspecified"))
      (node (ref "U3") (pin "2") (pinfunction "A1_2") (pintype "unspecified"))
      (node (ref "U3") (pin "20") (pinfunction "A4_20") (pintype "unspecified"))
      (node (ref "U3") (pin "23") (pinfunction "A2_23") (pintype "unspecified"))
      (node (ref "U3") (pin "5") (pinfunction "A3_5") (pintype "unspecified"))
      (node (ref "U30") (pin "2") (pinfunction "A1_2") (pintype "unspecified"))
      (node (ref "U30") (pin "20") (pinfunction "A4_20") (pintype "unspecified"))
      (node (ref "U30") (pin "23") (pinfunction "A2_23") (pintype "unspecified"))
      (node (ref "U30") (pin "5") (pinfunction "A3_5") (pintype "unspecified"))
      (node (ref "U32") (pin "2") (pinfunction "A1_2") (pintype "unspecified"))
      (node (ref "U32") (pin "20") (pinfunction "A4_20") (pintype "unspecified"))
      (node (ref "U32") (pin "23") (pinfunction "A2_23") (pintype "unspecified"))
      (node (ref "U32") (pin "5") (pinfunction "A3_5") (pintype "unspecified"))
      (node (ref "U33") (pin "2") (pinfunction "A1_2") (pintype "unspecified"))
      (node (ref "U33") (pin "20") (pinfunction "A4_20") (pintype "unspecified"))
      (node (ref "U33") (pin "23") (pinfunction "A2_23") (pintype "unspecified"))
      (node (ref "U33") (pin "5") (pinfunction "A3_5") (pintype "unspecified"))
      (node (ref "U36") (pin "2") (pinfunction "A1_2") (pintype "unspecified"))
      (node (ref "U36") (pin "20") (pinfunction "A4_20") (pintype "unspecified"))
      (node (ref "U36") (pin "23") (pinfunction "A2_23") (pintype "unspecified"))
      (node (ref "U36") (pin "5") (pinfunction "A3_5") (pintype "unspecified"))
      (node (ref "U40") (pin "2") (pinfunction "2_2") (pintype "unspecified"))
      (node (ref "U8") (pin "2") (pinfunction "A1_2") (pintype "unspecified"))
      (node (ref "U8") (pin "20") (pinfunction "A4_20") (pintype "unspecified"))
      (node (ref "U8") (pin "23") (pinfunction "A2_23") (pintype "unspecified"))
      (node (ref "U8") (pin "5") (pinfunction "A3_5") (pintype "unspecified"))
      (node (ref "U9") (pin "2") (pinfunction "A1_2") (pintype "unspecified"))
      (node (ref "U9") (pin "20") (pinfunction "A4_20") (pintype "unspecified"))
      (node (ref "U9") (pin "23") (pinfunction "A2_23") (pintype "unspecified"))
      (node (ref "U9") (pin "5") (pinfunction "A3_5") (pintype "unspecified"))
    )
    (net (code "2") (name "CLK") (class "Default")
      (node (ref "U1") (pin "12") (pinfunction "CLK/SCL_12") (pintype "unspecified"))
      (node (ref "U12") (pin "12") (pinfunction "CLK/SCL_12") (pintype "unspecified"))
      (node (ref "U13") (pin "12") (pinfunction "CLK/SCL_12") (pintype "unspecified"))
      (node (ref "U17") (pin "12") (pinfunction "CLK/SCL_12") (pintype "unspecified"))
      (node (ref "U18") (pin "12") (pinfunction "CLK/SCL_12") (pintype "unspecified"))
      (node (ref "U21") (pin "12") (pinfunction "CLK/SCL_12") (pintype "unspecified"))
      (node (ref "U22") (pin "12") (pinfunction "CLK/SCL_12") (pintype "unspecified"))
      (node (ref "U26") (pin "12") (pinfunction "CLK/SCL_12") (pintype "unspecified"))
      (node (ref "U27") (pin "12") (pinfunction "CLK/SCL_12") (pintype "unspecified"))
      (node (ref "U3") (pin "12") (pinfunction "CLK/SCL_12") (pintype "unspecified"))
      (node (ref "U30") (pin "12") (pinfunction "CLK/SCL_12") (pintype "unspecified"))
      (node (ref "U32") (pin "12") (pinfunction "CLK/SCL_12") (pintype "unspecified"))
      (node (ref "U33") (pin "12") (pinfunction "CLK/SCL_12") (pintype "unspecified"))
      (node (ref "U36") (pin "12") (pinfunction "CLK/SCL_12") (pintype "unspecified"))
      (node (ref "U37") (pin "5") (pinfunction "CLK_5") (pintype "unspecified"))
      (node (ref "U8") (pin "12") (pinfunction "CLK/SCL_12") (pintype "unspecified"))
      (node (ref "U9") (pin "12") (pinfunction "CLK/SCL_12") (pintype "unspecified"))
    )
    (net (code "3") (name "CS") (class "Default")
      (node (ref "U1") (pin "13") (pinfunction "#CS/AD0_13") (pintype "unspecified"))
      (node (ref "U12") (pin "13") (pinfunction "#CS/AD0_13") (pintype "unspecified"))
      (node (ref "U13") (pin "13") (pinfunction "#CS/AD0_13") (pintype "unspecified"))
      (node (ref "U17") (pin "13") (pinfunction "#CS/AD0_13") (pintype "unspecified"))
      (node (ref "U18") (pin "13") (pinfunction "#CS/AD0_13") (pintype "unspecified"))
      (node (ref "U21") (pin "13") (pinfunction "#CS/AD0_13") (pintype "unspecified"))
      (node (ref "U22") (pin "13") (pinfunction "#CS/AD0_13") (pintype "unspecified"))
      (node (ref "U26") (pin "13") (pinfunction "#CS/AD0_13") (pintype "unspecified"))
      (node (ref "U27") (pin "13") (pinfunction "#CS/AD0_13") (pintype "unspecified"))
      (node (ref "U3") (pin "13") (pinfunction "#CS/AD0_13") (pintype "unspecified"))
      (node (ref "U30") (pin "13") (pinfunction "#CS/AD0_13") (pintype "unspecified"))
      (node (ref "U32") (pin "13") (pinfunction "#CS/AD0_13") (pintype "unspecified"))
      (node (ref "U33") (pin "13") (pinfunction "#CS/AD0_13") (pintype "unspecified"))
      (node (ref "U36") (pin "13") (pinfunction "#CS/AD0_13") (pintype "unspecified"))
      (node (ref "U37") (pin "6") (pinfunction "CS_6") (pintype "unspecified"))
      (node (ref "U8") (pin "13") (pinfunction "#CS/AD0_13") (pintype "unspecified"))
      (node (ref "U9") (pin "13") (pinfunction "#CS/AD0_13") (pintype "unspecified"))
    )
    (net (code "4") (name "EXTERNAL5+") (class "Default")
      (node (ref "U41") (pin "1") (pinfunction "1_1") (pintype "unspecified"))
      (node (ref "U45") (pin "3") (pinfunction "3_3") (pintype "unspecified"))
    )
    (net (code "5") (name "EXTERNAL5-") (class "Default")
      (node (ref "U42") (pin "1") (pinfunction "1_1") (pintype "unspecified"))
      (node (ref "U45") (pin "2") (pinfunction "2_2") (pintype "unspecified"))
    )
    (net (code "6") (name "EXTERNAL5WAVES") (class "Default")
      (node (ref "U40") (pin "1") (pinfunction "1_1") (pintype "unspecified"))
      (node (ref "U45") (pin "1") (pinfunction "1_1") (pintype "unspecified"))
    )
    (net (code "7") (name "EXTERNAL12+") (class "Default")
      (node (ref "U43") (pin "1") (pinfunction "1_1") (pintype "unspecified"))
      (node (ref "U45") (pin "5") (pinfunction "5_5") (pintype "unspecified"))
    )
    (net (code "8") (name "EXTERNAL12-") (class "Default")
      (node (ref "U44") (pin "1") (pinfunction "1_1") (pintype "unspecified"))
      (node (ref "U45") (pin "4") (pinfunction "4_4") (pintype "unspecified"))
    )
    (net (code "9") (name "GND") (class "Default")
      (node (ref "C10") (pin "1") (pinfunction "1_1") (pintype "unspecified"))
      (node (ref "C17") (pin "2") (pinfunction "2_2") (pintype "unspecified"))
      (node (ref "C18") (pin "2") (pinfunction "2_2") (pintype "unspecified"))
      (node (ref "C20") (pin "2") (pinfunction "2_2") (pintype "unspecified"))
      (node (ref "C3") (pin "1") (pinfunction "1_1") (pintype "unspecified"))
      (node (ref "C4") (pin "2") (pinfunction "2_2") (pintype "unspecified"))
      (node (ref "C47") (pin "1") (pinfunction "1_1") (pintype "unspecified"))
      (node (ref "C48") (pin "2") (pinfunction "2_2") (pintype "unspecified"))
      (node (ref "C5") (pin "2") (pinfunction "2_2") (pintype "unspecified"))
      (node (ref "C50") (pin "1") (pinfunction "1_1") (pintype "unspecified"))
      (node (ref "C51") (pin "1") (pinfunction "1_1") (pintype "unspecified"))
      (node (ref "C6") (pin "2") (pinfunction "2_2") (pintype "unspecified"))
      (node (ref "C7") (pin "2") (pinfunction "2_2") (pintype "unspecified"))
      (node (ref "CN2") (pin "1") (pinfunction "1_1") (pintype "unspecified"))
      (node (ref "CN2") (pin "2") (pinfunction "2_2") (pintype "unspecified"))
      (node (ref "CN2") (pin "3") (pinfunction "3_3") (pintype "unspecified"))
      (node (ref "CN2") (pin "4") (pinfunction "4_4") (pintype "unspecified"))
      (node (ref "R101") (pin "1") (pinfunction "1_1") (pintype "unspecified"))
      (node (ref "R104") (pin "2") (pinfunction "2_2") (pintype "unspecified"))
      (node (ref "R105") (pin "2") (pinfunction "2_2") (pintype "unspecified"))
      (node (ref "R106") (pin "2") (pinfunction "2_2") (pintype "unspecified"))
      (node (ref "R107") (pin "2") (pinfunction "2_2") (pintype "unspecified"))
      (node (ref "R108") (pin "2") (pinfunction "2_2") (pintype "unspecified"))
      (node (ref "R109") (pin "2") (pinfunction "2_2") (pintype "unspecified"))
      (node (ref "R11") (pin "2") (pinfunction "2_2") (pintype "unspecified"))
      (node (ref "R112") (pin "1") (pinfunction "1_1") (pintype "unspecified"))
      (node (ref "R114") (pin "1") (pinfunction "1_1") (pintype "unspecified"))
      (node (ref "R117") (pin "1") (pinfunction "1_1") (pintype "unspecified"))
      (node (ref "R119") (pin "1") (pinfunction "1_1") (pintype "unspecified"))
      (node (ref "R12") (pin "1") (pinfunction "1_1") (pintype "unspecified"))
      (node (ref "R122") (pin "2") (pinfunction "2_2") (pintype "unspecified"))
      (node (ref "R123") (pin "2") (pinfunction "2_2") (pintype "unspecified"))
      (node (ref "R126") (pin "1") (pinfunction "1_1") (pintype "unspecified"))
      (node (ref "R128") (pin "1") (pinfunction "1_1") (pintype "unspecified"))
      (node (ref "R13") (pin "2") (pinfunction "2_2") (pintype "unspecified"))
      (node (ref "R133") (pin "2") (pinfunction "2_2") (pintype "unspecified"))
      (node (ref "R134") (pin "2") (pinfunction "2_2") (pintype "unspecified"))
      (node (ref "R135") (pin "2") (pinfunction "2_2") (pintype "unspecified"))
      (node (ref "R137") (pin "2") (pinfunction "2_2") (pintype "unspecified"))
      (node (ref "R138") (pin "2") (pinfunction "2_2") (pintype "unspecified"))
      (node (ref "R14") (pin "2") (pinfunction "2_2") (pintype "unspecified"))
      (node (ref "R141") (pin "1") (pinfunction "1_1") (pintype "unspecified"))
      (node (ref "R143") (pin "1") (pinfunction "1_1") (pintype "unspecified"))
      (node (ref "R146") (pin "1") (pinfunction "1_1") (pintype "unspecified"))
      (node (ref "R148") (pin "1") (pinfunction "1_1") (pintype "unspecified"))
      (node (ref "R15") (pin "2") (pinfunction "2_2") (pintype "unspecified"))
      (node (ref "R151") (pin "2") (pinfunction "2_2") (pintype "unspecified"))
      (node (ref "R152") (pin "2") (pinfunction "2_2") (pintype "unspecified"))
      (node (ref "R153") (pin "2") (pinfunction "2_2") (pintype "unspecified"))
      (node (ref "R18") (pin "1") (pinfunction "1_1") (pintype "unspecified"))
      (node (ref "R2") (pin "1") (pinfunction "1_1") (pintype "unspecified"))
      (node (ref "R20") (pin "1") (pinfunction "1_1") (pintype "unspecified"))
      (node (ref "R21") (pin "2") (pinfunction "2_2") (pintype "unspecified"))
      (node (ref "R24") (pin "1") (pinfunction "1_1") (pintype "unspecified"))
      (node (ref "R26") (pin "2") (pinfunction "2_2") (pintype "unspecified"))
      (node (ref "R29") (pin "1") (pinfunction "1_1") (pintype "unspecified"))
      (node (ref "R32") (pin "2") (pinfunction "2_2") (pintype "unspecified"))
      (node (ref "R33") (pin "2") (pinfunction "2_2") (pintype "unspecified"))
      (node (ref "R34") (pin "2") (pinfunction "2_2") (pintype "unspecified"))
      (node (ref "R35") (pin "2") (pinfunction "2_2") (pintype "unspecified"))
      (node (ref "R36") (pin "2") (pinfunction "2_2") (pintype "unspecified"))
      (node (ref "R37") (pin "2") (pinfunction "2_2") (pintype "unspecified"))
      (node (ref "R4") (pin "1") (pinfunction "1_1") (pintype "unspecified"))
      (node (ref "R40") (pin "1") (pinfunction "1_1") (pintype "unspecified"))
      (node (ref "R42") (pin "1") (pinfunction "1_1") (pintype "unspecified"))
      (node (ref "R45") (pin "1") (pinfunction "1_1") (pintype "unspecified"))
      (node (ref "R47") (pin "1") (pinfunction "1_1") (pintype "unspecified"))
      (node (ref "R50") (pin "2") (pinfunction "2_2") (pintype "unspecified"))
      (node (ref "R51") (pin "2") (pinfunction "2_2") (pintype "unspecified"))
      (node (ref "R52") (pin "2") (pinfunction "2_2") (pintype "unspecified"))
      (node (ref "R53") (pin "2") (pinfunction "2_2") (pintype "unspecified"))
      (node (ref "R54") (pin "2") (pinfunction "2_2") (pintype "unspecified"))
      (node (ref "R55") (pin "2") (pinfunction "2_2") (pintype "unspecified"))
      (node (ref "R58") (pin "1") (pinfunction "1_1") (pintype "unspecified"))
      (node (ref "R60") (pin "1") (pinfunction "1_1") (pintype "unspecified"))
      (node (ref "R63") (pin "1") (pinfunction "1_1") (pintype "unspecified"))
      (node (ref "R65") (pin "1") (pinfunction "1_1") (pintype "unspecified"))
      (node (ref "R68") (pin "2") (pinfunction "2_2") (pintype "unspecified"))
      (node (ref "R69") (pin "2") (pinfunction "2_2") (pintype "unspecified"))
      (node (ref "R7") (pin "2") (pinfunction "2_2") (pintype "unspecified"))
      (node (ref "R70") (pin "2") (pinfunction "2_2") (pintype "unspecified"))
      (node (ref "R71") (pin "2") (pinfunction "2_2") (pintype "unspecified"))
      (node (ref "R72") (pin "2") (pinfunction "2_2") (pintype "unspecified"))
      (node (ref "R73") (pin "2") (pinfunction "2_2") (pintype "unspecified"))
      (node (ref "R76") (pin "1") (pinfunction "1_1") (pintype "unspecified"))
      (node (ref "R78") (pin "1") (pinfunction "1_1") (pintype "unspecified"))
      (node (ref "R8") (pin "2") (pinfunction "2_2") (pintype "unspecified"))
      (node (ref "R81") (pin "1") (pinfunction "1_1") (pintype "unspecified"))
      (node (ref "R83") (pin "1") (pinfunction "1_1") (pintype "unspecified"))
      (node (ref "R86") (pin "2") (pinfunction "2_2") (pintype "unspecified"))
      (node (ref "R87") (pin "2") (pinfunction "2_2") (pintype "unspecified"))
      (node (ref "R88") (pin "2") (pinfunction "2_2") (pintype "unspecified"))
      (node (ref "R89") (pin "2") (pinfunction "2_2") (pintype "unspecified"))
      (node (ref "R90") (pin "2") (pinfunction "2_2") (pintype "unspecified"))
      (node (ref "R91") (pin "2") (pinfunction "2_2") (pintype "unspecified"))
      (node (ref "R94") (pin "1") (pinfunction "1_1") (pintype "unspecified"))
      (node (ref "R96") (pin "1") (pinfunction "1_1") (pintype "unspecified"))
      (node (ref "R99") (pin "1") (pinfunction "1_1") (pintype "unspecified"))
      (node (ref "U1") (pin "1") (pinfunction "B1_1") (pintype "unspecified"))
      (node (ref "U1") (pin "21") (pinfunction "B4_21") (pintype "unspecified"))
      (node (ref "U1") (pin "24") (pinfunction "B2_24") (pintype "unspecified"))
      (node (ref "U1") (pin "4") (pinfunction "B3_4") (pintype "unspecified"))
      (node (ref "U1") (pin "8") (pinfunction "GND_8") (pintype "unspecified"))
      (node (ref "U1") (pin "9") (pinfunction "DIS_9") (pintype "unspecified"))
      (node (ref "U12") (pin "1") (pinfunction "B1_1") (pintype "unspecified"))
      (node (ref "U12") (pin "21") (pinfunction "B4_21") (pintype "unspecified"))
      (node (ref "U12") (pin "24") (pinfunction "B2_24") (pintype "unspecified"))
      (node (ref "U12") (pin "4") (pinfunction "B3_4") (pintype "unspecified"))
      (node (ref "U12") (pin "8") (pinfunction "GND_8") (pintype "unspecified"))
      (node (ref "U12") (pin "9") (pinfunction "DIS_9") (pintype "unspecified"))
      (node (ref "U13") (pin "1") (pinfunction "B1_1") (pintype "unspecified"))
      (node (ref "U13") (pin "21") (pinfunction "B4_21") (pintype "unspecified"))
      (node (ref "U13") (pin "24") (pinfunction "B2_24") (pintype "unspecified"))
      (node (ref "U13") (pin "4") (pinfunction "B3_4") (pintype "unspecified"))
      (node (ref "U13") (pin "8") (pinfunction "GND_8") (pintype "unspecified"))
      (node (ref "U13") (pin "9") (pinfunction "DIS_9") (pintype "unspecified"))
      (node (ref "U17") (pin "1") (pinfunction "B1_1") (pintype "unspecified"))
      (node (ref "U17") (pin "21") (pinfunction "B4_21") (pintype "unspecified"))
      (node (ref "U17") (pin "24") (pinfunction "B2_24") (pintype "unspecified"))
      (node (ref "U17") (pin "4") (pinfunction "B3_4") (pintype "unspecified"))
      (node (ref "U17") (pin "8") (pinfunction "GND_8") (pintype "unspecified"))
      (node (ref "U17") (pin "9") (pinfunction "DIS_9") (pintype "unspecified"))
      (node (ref "U18") (pin "1") (pinfunction "B1_1") (pintype "unspecified"))
      (node (ref "U18") (pin "21") (pinfunction "B4_21") (pintype "unspecified"))
      (node (ref "U18") (pin "24") (pinfunction "B2_24") (pintype "unspecified"))
      (node (ref "U18") (pin "4") (pinfunction "B3_4") (pintype "unspecified"))
      (node (ref "U18") (pin "8") (pinfunction "GND_8") (pintype "unspecified"))
      (node (ref "U18") (pin "9") (pinfunction "DIS_9") (pintype "unspecified"))
      (node (ref "U21") (pin "1") (pinfunction "B1_1") (pintype "unspecified"))
      (node (ref "U21") (pin "21") (pinfunction "B4_21") (pintype "unspecified"))
      (node (ref "U21") (pin "24") (pinfunction "B2_24") (pintype "unspecified"))
      (node (ref "U21") (pin "4") (pinfunction "B3_4") (pintype "unspecified"))
      (node (ref "U21") (pin "8") (pinfunction "GND_8") (pintype "unspecified"))
      (node (ref "U21") (pin "9") (pinfunction "DIS_9") (pintype "unspecified"))
      (node (ref "U22") (pin "1") (pinfunction "B1_1") (pintype "unspecified"))
      (node (ref "U22") (pin "21") (pinfunction "B4_21") (pintype "unspecified"))
      (node (ref "U22") (pin "24") (pinfunction "B2_24") (pintype "unspecified"))
      (node (ref "U22") (pin "4") (pinfunction "B3_4") (pintype "unspecified"))
      (node (ref "U22") (pin "8") (pinfunction "GND_8") (pintype "unspecified"))
      (node (ref "U22") (pin "9") (pinfunction "DIS_9") (pintype "unspecified"))
      (node (ref "U26") (pin "1") (pinfunction "B1_1") (pintype "unspecified"))
      (node (ref "U26") (pin "21") (pinfunction "B4_21") (pintype "unspecified"))
      (node (ref "U26") (pin "24") (pinfunction "B2_24") (pintype "unspecified"))
      (node (ref "U26") (pin "4") (pinfunction "B3_4") (pintype "unspecified"))
      (node (ref "U26") (pin "8") (pinfunction "GND_8") (pintype "unspecified"))
      (node (ref "U26") (pin "9") (pinfunction "DIS_9") (pintype "unspecified"))
      (node (ref "U27") (pin "1") (pinfunction "B1_1") (pintype "unspecified"))
      (node (ref "U27") (pin "21") (pinfunction "B4_21") (pintype "unspecified"))
      (node (ref "U27") (pin "24") (pinfunction "B2_24") (pintype "unspecified"))
      (node (ref "U27") (pin "4") (pinfunction "B3_4") (pintype "unspecified"))
      (node (ref "U27") (pin "8") (pinfunction "GND_8") (pintype "unspecified"))
      (node (ref "U27") (pin "9") (pinfunction "DIS_9") (pintype "unspecified"))
      (node (ref "U3") (pin "1") (pinfunction "B1_1") (pintype "unspecified"))
      (node (ref "U3") (pin "21") (pinfunction "B4_21") (pintype "unspecified"))
      (node (ref "U3") (pin "24") (pinfunction "B2_24") (pintype "unspecified"))
      (node (ref "U3") (pin "4") (pinfunction "B3_4") (pintype "unspecified"))
      (node (ref "U3") (pin "8") (pinfunction "GND_8") (pintype "unspecified"))
      (node (ref "U3") (pin "9") (pinfunction "DIS_9") (pintype "unspecified"))
      (node (ref "U30") (pin "1") (pinfunction "B1_1") (pintype "unspecified"))
      (node (ref "U30") (pin "21") (pinfunction "B4_21") (pintype "unspecified"))
      (node (ref "U30") (pin "24") (pinfunction "B2_24") (pintype "unspecified"))
      (node (ref "U30") (pin "4") (pinfunction "B3_4") (pintype "unspecified"))
      (node (ref "U30") (pin "8") (pinfunction "GND_8") (pintype "unspecified"))
      (node (ref "U30") (pin "9") (pinfunction "DIS_9") (pintype "unspecified"))
      (node (ref "U32") (pin "1") (pinfunction "B1_1") (pintype "unspecified"))
      (node (ref "U32") (pin "21") (pinfunction "B4_21") (pintype "unspecified"))
      (node (ref "U32") (pin "24") (pinfunction "B2_24") (pintype "unspecified"))
      (node (ref "U32") (pin "4") (pinfunction "B3_4") (pintype "unspecified"))
      (node (ref "U32") (pin "8") (pinfunction "GND_8") (pintype "unspecified"))
      (node (ref "U32") (pin "9") (pinfunction "DIS_9") (pintype "unspecified"))
      (node (ref "U33") (pin "1") (pinfunction "B1_1") (pintype "unspecified"))
      (node (ref "U33") (pin "21") (pinfunction "B4_21") (pintype "unspecified"))
      (node (ref "U33") (pin "24") (pinfunction "B2_24") (pintype "unspecified"))
      (node (ref "U33") (pin "4") (pinfunction "B3_4") (pintype "unspecified"))
      (node (ref "U33") (pin "8") (pinfunction "GND_8") (pintype "unspecified"))
      (node (ref "U33") (pin "9") (pinfunction "DIS_9") (pintype "unspecified"))
      (node (ref "U36") (pin "1") (pinfunction "B1_1") (pintype "unspecified"))
      (node (ref "U36") (pin "21") (pinfunction "B4_21") (pintype "unspecified"))
      (node (ref "U36") (pin "24") (pinfunction "B2_24") (pintype "unspecified"))
      (node (ref "U36") (pin "4") (pinfunction "B3_4") (pintype "unspecified"))
      (node (ref "U36") (pin "8") (pinfunction "GND_8") (pintype "unspecified"))
      (node (ref "U36") (pin "9") (pinfunction "DIS_9") (pintype "unspecified"))
      (node (ref "U37") (pin "4") (pinfunction "AGND_4") (pintype "unspecified"))
      (node (ref "U38") (pin "2") (pinfunction "GND_2") (pintype "unspecified"))
      (node (ref "U4") (pin "A3") (pinfunction "GND_A3") (pintype "unspecified"))
      (node (ref "U4") (pin "A4") (pinfunction "GND_A4") (pintype "unspecified"))
      (node (ref "U4") (pin "B3") (pinfunction "GND_B3") (pintype "unspecified"))
      (node (ref "U4") (pin "B4") (pinfunction "GND_B4") (pintype "unspecified"))
      (node (ref "U4") (pin "B5") (pinfunction "GND_B5") (pintype "unspecified"))
      (node (ref "U4") (pin "B6") (pinfunction "GND_B6") (pintype "unspecified"))
      (node (ref "U4") (pin "C2") (pinfunction "VOUT1N_C2") (pintype "unspecified"))
      (node (ref "U4") (pin "C3") (pinfunction "GND_C3") (pintype "unspecified"))
      (node (ref "U4") (pin "C4") (pinfunction "GND_C4") (pintype "unspecified"))
      (node (ref "U4") (pin "C5") (pinfunction "GND_C5") (pintype "unspecified"))
      (node (ref "U4") (pin "C6") (pinfunction "GND_C6") (pintype "unspecified"))
      (node (ref "U4") (pin "D1") (pinfunction "VOUT1N_D1") (pintype "unspecified"))
      (node (ref "U4") (pin "D2") (pinfunction "VOUT1N_D2") (pintype "unspecified"))
      (node (ref "U4") (pin "D3") (pinfunction "GND_D3") (pintype "unspecified"))
      (node (ref "U4") (pin "D4") (pinfunction "GND_D4") (pintype "unspecified"))
      (node (ref "U4") (pin "D5") (pinfunction "GND_D5") (pintype "unspecified"))
      (node (ref "U4") (pin "D7") (pinfunction "SYNC1_D7") (pintype "unspecified"))
      (node (ref "U4") (pin "E1") (pinfunction "VOUT1N_E1") (pintype "unspecified"))
      (node (ref "U4") (pin "E2") (pinfunction "VOUT1N_E2") (pintype "unspecified"))
      (node (ref "U4") (pin "E3") (pinfunction "GND_E3") (pintype "unspecified"))
      (node (ref "U4") (pin "E4") (pinfunction "GND_E4") (pintype "unspecified"))
      (node (ref "U4") (pin "E5") (pinfunction "GND_E5") (pintype "unspecified"))
      (node (ref "U4") (pin "F1") (pinfunction "GND_F1") (pintype "unspecified"))
      (node (ref "U4") (pin "F2") (pinfunction "GND_F2") (pintype "unspecified"))
      (node (ref "U4") (pin "F5") (pinfunction "GND_F5") (pintype "unspecified"))
      (node (ref "U4") (pin "F6") (pinfunction "GND_F6") (pintype "unspecified"))
      (node (ref "U4") (pin "F7") (pinfunction "GND_F7") (pintype "unspecified"))
      (node (ref "U4") (pin "G3") (pinfunction "GND_G3") (pintype "unspecified"))
      (node (ref "U4") (pin "G4") (pinfunction "GND_G4") (pintype "unspecified"))
      (node (ref "U4") (pin "G5") (pinfunction "GND_G5") (pintype "unspecified"))
      (node (ref "U4") (pin "H3") (pinfunction "GND_H3") (pintype "unspecified"))
      (node (ref "U4") (pin "H4") (pinfunction "GND_H4") (pintype "unspecified"))
      (node (ref "U4") (pin "H5") (pinfunction "GND_H5") (pintype "unspecified"))
      (node (ref "U4") (pin "J3") (pinfunction "GND_J3") (pintype "unspecified"))
      (node (ref "U4") (pin "J4") (pinfunction "GND_J4") (pintype "unspecified"))
      (node (ref "U4") (pin "J5") (pinfunction "GND_J5") (pintype "unspecified"))
      (node (ref "U4") (pin "J6") (pinfunction "GND_J6") (pintype "unspecified"))
      (node (ref "U4") (pin "K1") (pinfunction "VOUT2P_K1") (pintype "unspecified"))
      (node (ref "U4") (pin "K2") (pinfunction "VOUT2P_K2") (pintype "unspecified"))
      (node (ref "U4") (pin "K3") (pinfunction "GND_K3") (pintype "unspecified"))
      (node (ref "U4") (pin "K4") (pinfunction "GND_K4") (pintype "unspecified"))
      (node (ref "U4") (pin "K5") (pinfunction "GND_K5") (pintype "unspecified"))
      (node (ref "U4") (pin "K6") (pinfunction "GND_K6") (pintype "unspecified"))
      (node (ref "U4") (pin "L1") (pinfunction "VOUT2P_L1") (pintype "unspecified"))
      (node (ref "U4") (pin "L2") (pinfunction "VOUT2P_L2") (pintype "unspecified"))
      (node (ref "U4") (pin "L3") (pinfunction "GND_L3") (pintype "unspecified"))
      (node (ref "U4") (pin "L4") (pinfunction "GND_L4") (pintype "unspecified"))
      (node (ref "U45") (pin "6") (pinfunction "6_6") (pintype "unspecified"))
      (node (ref "U6") (pin "15") (pinfunction "GND_15") (pintype "unspecified"))
      (node (ref "U6") (pin "4") (pinfunction "GND_4") (pintype "unspecified"))
      (node (ref "U6") (pin "5") (pinfunction "GND_5") (pintype "unspecified"))
      (node (ref "U8") (pin "1") (pinfunction "B1_1") (pintype "unspecified"))
      (node (ref "U8") (pin "21") (pinfunction "B4_21") (pintype "unspecified"))
      (node (ref "U8") (pin "24") (pinfunction "B2_24") (pintype "unspecified"))
      (node (ref "U8") (pin "4") (pinfunction "B3_4") (pintype "unspecified"))
      (node (ref "U8") (pin "8") (pinfunction "GND_8") (pintype "unspecified"))
      (node (ref "U8") (pin "9") (pinfunction "DIS_9") (pintype "unspecified"))
      (node (ref "U9") (pin "1") (pinfunction "B1_1") (pintype "unspecified"))
      (node (ref "U9") (pin "21") (pinfunction "B4_21") (pintype "unspecified"))
      (node (ref "U9") (pin "24") (pinfunction "B2_24") (pintype "unspecified"))
      (node (ref "U9") (pin "4") (pinfunction "B3_4") (pintype "unspecified"))
      (node (ref "U9") (pin "8") (pinfunction "GND_8") (pintype "unspecified"))
      (node (ref "U9") (pin "9") (pinfunction "DIS_9") (pintype "unspecified"))
    )
    (net (code "10") (name "MISO") (class "Default")
      (node (ref "U33") (pin "16") (pinfunction "SDO/O1_16") (pintype "unspecified"))
      (node (ref "U37") (pin "2") (pinfunction "MISO_2") (pintype "unspecified"))
    )
    (net (code "11") (name "MOSI") (class "Default")
      (node (ref "U1") (pin "11") (pinfunction "SDI/SDA_11") (pintype "unspecified"))
      (node (ref "U37") (pin "1") (pinfunction "MOSI_1") (pintype "unspecified"))
    )
    (net (code "12") (name "Net-(U1-SDO{slash}O1)") (class "Default")
      (node (ref "R21") (pin "1") (pinfunction "1_1") (pintype "unspecified"))
      (node (ref "U1") (pin "16") (pinfunction "SDO/O1_16") (pintype "unspecified"))
      (node (ref "U3") (pin "11") (pinfunction "SDI/SDA_11") (pintype "unspecified"))
    )
    (net (code "13") (name "Net-(U1-W1)") (class "Default")
      (node (ref "U1") (pin "3") (pinfunction "W1_3") (pintype "unspecified"))
      (node (ref "U2") (pin "3") (pinfunction "+INA_3") (pintype "unspecified"))
    )
    (net (code "14") (name "Net-(U1-W2)") (class "Default")
      (node (ref "U1") (pin "22") (pinfunction "W2_22") (pintype "unspecified"))
      (node (ref "U2") (pin "12") (pinfunction "+IND_12") (pintype "unspecified"))
    )
    (net (code "15") (name "Net-(U1-W3)") (class "Default")
      (node (ref "U1") (pin "6") (pinfunction "W3_6") (pintype "unspecified"))
      (node (ref "U2") (pin "5") (pinfunction "+INB_5") (pintype "unspecified"))
    )
    (net (code "16") (name "Net-(U1-W4)") (class "Default")
      (node (ref "U1") (pin "19") (pinfunction "W4_19") (pintype "unspecified"))
      (node (ref "U2") (pin "10") (pinfunction "+INC_10") (pintype "unspecified"))
    )
    (net (code "17") (name "Net-(U2--INA)") (class "Default")
      (node (ref "R1") (pin "2") (pinfunction "2_2") (pintype "unspecified"))
      (node (ref "R2") (pin "2") (pinfunction "2_2") (pintype "unspecified"))
      (node (ref "U2") (pin "2") (pinfunction "-INA_2") (pintype "unspecified"))
    )
    (net (code "18") (name "Net-(U2--INB)") (class "Default")
      (node (ref "R3") (pin "1") (pinfunction "1_1") (pintype "unspecified"))
      (node (ref "R4") (pin "2") (pinfunction "2_2") (pintype "unspecified"))
      (node (ref "U2") (pin "6") (pinfunction "-INB_6") (pintype "unspecified"))
    )
    (net (code "19") (name "Net-(U2--INC)") (class "Default")
      (node (ref "R6") (pin "1") (pinfunction "1_1") (pintype "unspecified"))
      (node (ref "R7") (pin "1") (pinfunction "1_1") (pintype "unspecified"))
      (node (ref "U2") (pin "9") (pinfunction "-INC_9") (pintype "unspecified"))
    )
    (net (code "20") (name "Net-(U2--IND)") (class "Default")
      (node (ref "R5") (pin "2") (pinfunction "2_2") (pintype "unspecified"))
      (node (ref "R8") (pin "1") (pinfunction "1_1") (pintype "unspecified"))
      (node (ref "U2") (pin "13") (pinfunction "-IND_13") (pintype "unspecified"))
    )
    (net (code "21") (name "Net-(U2-OUTA)") (class "Default")
      (node (ref "R1") (pin "1") (pinfunction "1_1") (pintype "unspecified"))
      (node (ref "U2") (pin "1") (pinfunction "OUTA_1") (pintype "unspecified"))
      (node (ref "U39") (pin "4") (pinfunction "4_4") (pintype "unspecified"))
    )
    (net (code "22") (name "Net-(U2-OUTB)") (class "Default")
      (node (ref "R3") (pin "2") (pinfunction "2_2") (pintype "unspecified"))
      (node (ref "U2") (pin "7") (pinfunction "OUTB_7") (pintype "unspecified"))
      (node (ref "U39") (pin "2") (pinfunction "2_2") (pintype "unspecified"))
    )
    (net (code "23") (name "Net-(U2-OUTC)") (class "Default")
      (node (ref "R6") (pin "2") (pinfunction "2_2") (pintype "unspecified"))
      (node (ref "U2") (pin "8") (pinfunction "OUTC_8") (pintype "unspecified"))
      (node (ref "U39") (pin "1") (pinfunction "1_1") (pintype "unspecified"))
    )
    (net (code "24") (name "Net-(U2-OUTD)") (class "Default")
      (node (ref "R5") (pin "1") (pinfunction "1_1") (pintype "unspecified"))
      (node (ref "U2") (pin "14") (pinfunction "OUTD_14") (pintype "unspecified"))
      (node (ref "U39") (pin "3") (pinfunction "3_3") (pintype "unspecified"))
    )
    (net (code "25") (name "Net-(U3-SDO{slash}O1)") (class "Default")
      (node (ref "R13") (pin "1") (pinfunction "1_1") (pintype "unspecified"))
      (node (ref "U3") (pin "16") (pinfunction "SDO/O1_16") (pintype "unspecified"))
      (node (ref "U8") (pin "11") (pinfunction "SDI/SDA_11") (pintype "unspecified"))
    )
    (net (code "26") (name "Net-(U3-W1)") (class "Default")
      (node (ref "U3") (pin "3") (pinfunction "W1_3") (pintype "unspecified"))
      (node (ref "U5") (pin "3") (pinfunction "+INA_3") (pintype "unspecified"))
    )
    (net (code "27") (name "Net-(U3-W2)") (class "Default")
      (node (ref "U3") (pin "22") (pinfunction "W2_22") (pintype "unspecified"))
      (node (ref "U5") (pin "12") (pinfunction "+IND_12") (pintype "unspecified"))
    )
    (net (code "28") (name "Net-(U3-W3)") (class "Default")
      (node (ref "U3") (pin "6") (pinfunction "W3_6") (pintype "unspecified"))
      (node (ref "U5") (pin "5") (pinfunction "+INB_5") (pintype "unspecified"))
    )
    (net (code "29") (name "Net-(U3-W4)") (class "Default")
      (node (ref "U3") (pin "19") (pinfunction "W4_19") (pintype "unspecified"))
      (node (ref "U5") (pin "10") (pinfunction "+INC_10") (pintype "unspecified"))
    )
    (net (code "30") (name "Net-(U4-CLKOUT1)") (class "Default")
      (node (ref "U4") (pin "E6") (pinfunction "CLKOUT1_E6") (pintype "unspecified"))
      (node (ref "U4") (pin "H7") (pinfunction "SYNC2_H7") (pintype "unspecified"))
    )
    (net (code "31") (name "Net-(U4-FBX1)") (class "Default")
      (node (ref "R10") (pin "2") (pinfunction "2_2") (pintype "unspecified"))
      (node (ref "U4") (pin "C1") (pinfunction "FBX1_C1") (pintype "unspecified"))
    )
    (net (code "32") (name "Net-(U4-FBX2)") (class "Default")
      (node (ref "R9") (pin "2") (pinfunction "2_2") (pintype "unspecified"))
      (node (ref "U4") (pin "J1") (pinfunction "FBX2_J1") (pintype "unspecified"))
    )
    (net (code "33") (name "Net-(U4-RT1)") (class "Default")
      (node (ref "R11") (pin "1") (pinfunction "1_1") (pintype "unspecified"))
      (node (ref "U4") (pin "E7") (pinfunction "RT1_E7") (pintype "unspecified"))
    )
    (net (code "34") (name "Net-(U4-RT2)") (class "Default")
      (node (ref "R12") (pin "2") (pinfunction "2_2") (pintype "unspecified"))
      (node (ref "U4") (pin "G7") (pinfunction "RT2_G7") (pintype "unspecified"))
    )
    (net (code "35") (name "Net-(U4-SS1)") (class "Default")
      (node (ref "C48") (pin "1") (pinfunction "1_1") (pintype "unspecified"))
      (node (ref "U4") (pin "C7") (pinfunction "SS1_C7") (pintype "unspecified"))
    )
    (net (code "36") (name "Net-(U4-SS2)") (class "Default")
      (node (ref "C3") (pin "2") (pinfunction "2_2") (pintype "unspecified"))
      (node (ref "U4") (pin "J7") (pinfunction "SS2_J7") (pintype "unspecified"))
    )
    (net (code "37") (name "Net-(U5--INA)") (class "Default")
      (node (ref "R20") (pin "2") (pinfunction "2_2") (pintype "unspecified"))
      (node (ref "R22") (pin "2") (pinfunction "2_2") (pintype "unspecified"))
      (node (ref "U5") (pin "2") (pinfunction "-INA_2") (pintype "unspecified"))
    )
    (net (code "38") (name "Net-(U5--INB)") (class "Default")
      (node (ref "R18") (pin "2") (pinfunction "2_2") (pintype "unspecified"))
      (node (ref "R19") (pin "1") (pinfunction "1_1") (pintype "unspecified"))
      (node (ref "U5") (pin "6") (pinfunction "-INB_6") (pintype "unspecified"))
    )
    (net (code "39") (name "Net-(U5--INC)") (class "Default")
      (node (ref "R15") (pin "1") (pinfunction "1_1") (pintype "unspecified"))
      (node (ref "R16") (pin "1") (pinfunction "1_1") (pintype "unspecified"))
      (node (ref "U5") (pin "9") (pinfunction "-INC_9") (pintype "unspecified"))
    )
    (net (code "40") (name "Net-(U5--IND)") (class "Default")
      (node (ref "R14") (pin "1") (pinfunction "1_1") (pintype "unspecified"))
      (node (ref "R17") (pin "2") (pinfunction "2_2") (pintype "unspecified"))
      (node (ref "U5") (pin "13") (pinfunction "-IND_13") (pintype "unspecified"))
    )
    (net (code "41") (name "Net-(U5-OUTA)") (class "Default")
      (node (ref "R22") (pin "1") (pinfunction "1_1") (pintype "unspecified"))
      (node (ref "U46") (pin "4") (pinfunction "4_4") (pintype "unspecified"))
      (node (ref "U5") (pin "1") (pinfunction "OUTA_1") (pintype "unspecified"))
    )
    (net (code "42") (name "Net-(U5-OUTB)") (class "Default")
      (node (ref "R19") (pin "2") (pinfunction "2_2") (pintype "unspecified"))
      (node (ref "U46") (pin "2") (pinfunction "2_2") (pintype "unspecified"))
      (node (ref "U5") (pin "7") (pinfunction "OUTB_7") (pintype "unspecified"))
    )
    (net (code "43") (name "Net-(U5-OUTC)") (class "Default")
      (node (ref "R16") (pin "2") (pinfunction "2_2") (pintype "unspecified"))
      (node (ref "U46") (pin "1") (pinfunction "1_1") (pintype "unspecified"))
      (node (ref "U5") (pin "8") (pinfunction "OUTC_8") (pintype "unspecified"))
    )
    (net (code "44") (name "Net-(U5-OUTD)") (class "Default")
      (node (ref "R17") (pin "1") (pinfunction "1_1") (pintype "unspecified"))
      (node (ref "U46") (pin "3") (pinfunction "3_3") (pintype "unspecified"))
      (node (ref "U5") (pin "14") (pinfunction "OUTD_14") (pintype "unspecified"))
    )
    (net (code "45") (name "Net-(U6-BYPN)") (class "Default")
      (node (ref "C9") (pin "1") (pinfunction "1_1") (pintype "unspecified"))
      (node (ref "U6") (pin "11") (pinfunction "BYPN_11") (pintype "unspecified"))
    )
    (net (code "46") (name "Net-(U6-BYPP)") (class "Default")
      (node (ref "C8") (pin "1") (pinfunction "1_1") (pintype "unspecified"))
      (node (ref "U6") (pin "3") (pinfunction "BYPP_3") (pintype "unspecified"))
    )
    (net (code "47") (name "Net-(U7-+INA)") (class "Default")
      (node (ref "U7") (pin "3") (pinfunction "+INA_3") (pintype "unspecified"))
      (node (ref "U8") (pin "3") (pinfunction "W1_3") (pintype "unspecified"))
    )
    (net (code "48") (name "Net-(U7-+INB)") (class "Default")
      (node (ref "U7") (pin "5") (pinfunction "+INB_5") (pintype "unspecified"))
      (node (ref "U8") (pin "6") (pinfunction "W3_6") (pintype "unspecified"))
    )
    (net (code "49") (name "Net-(U7-+INC)") (class "Default")
      (node (ref "U7") (pin "10") (pinfunction "+INC_10") (pintype "unspecified"))
      (node (ref "U8") (pin "19") (pinfunction "W4_19") (pintype "unspecified"))
    )
    (net (code "50") (name "Net-(U7-+IND)") (class "Default")
      (node (ref "U7") (pin "12") (pinfunction "+IND_12") (pintype "unspecified"))
      (node (ref "U8") (pin "22") (pinfunction "W2_22") (pintype "unspecified"))
    )
    (net (code "51") (name "Net-(U7--INA)") (class "Default")
      (node (ref "R23") (pin "2") (pinfunction "2_2") (pintype "unspecified"))
      (node (ref "R24") (pin "2") (pinfunction "2_2") (pintype "unspecified"))
      (node (ref "U7") (pin "2") (pinfunction "-INA_2") (pintype "unspecified"))
    )
    (net (code "52") (name "Net-(U7--INB)") (class "Default")
      (node (ref "R25") (pin "1") (pinfunction "1_1") (pintype "unspecified"))
      (node (ref "R29") (pin "2") (pinfunction "2_2") (pintype "unspecified"))
      (node (ref "U7") (pin "6") (pinfunction "-INB_6") (pintype "unspecified"))
    )
    (net (code "53") (name "Net-(U7--INC)") (class "Default")
      (node (ref "R31") (pin "1") (pinfunction "1_1") (pintype "unspecified"))
      (node (ref "R32") (pin "1") (pinfunction "1_1") (pintype "unspecified"))
      (node (ref "U7") (pin "9") (pinfunction "-INC_9") (pintype "unspecified"))
    )
    (net (code "54") (name "Net-(U7--IND)") (class "Default")
      (node (ref "R30") (pin "2") (pinfunction "2_2") (pintype "unspecified"))
      (node (ref "R33") (pin "1") (pinfunction "1_1") (pintype "unspecified"))
      (node (ref "U7") (pin "13") (pinfunction "-IND_13") (pintype "unspecified"))
    )
    (net (code "55") (name "Net-(U7-OUTA)") (class "Default")
      (node (ref "R23") (pin "1") (pinfunction "1_1") (pintype "unspecified"))
      (node (ref "U47") (pin "4") (pinfunction "4_4") (pintype "unspecified"))
      (node (ref "U7") (pin "1") (pinfunction "OUTA_1") (pintype "unspecified"))
    )
    (net (code "56") (name "Net-(U7-OUTB)") (class "Default")
      (node (ref "R25") (pin "2") (pinfunction "2_2") (pintype "unspecified"))
      (node (ref "U47") (pin "2") (pinfunction "2_2") (pintype "unspecified"))
      (node (ref "U7") (pin "7") (pinfunction "OUTB_7") (pintype "unspecified"))
    )
    (net (code "57") (name "Net-(U7-OUTC)") (class "Default")
      (node (ref "R31") (pin "2") (pinfunction "2_2") (pintype "unspecified"))
      (node (ref "U47") (pin "1") (pinfunction "1_1") (pintype "unspecified"))
      (node (ref "U7") (pin "8") (pinfunction "OUTC_8") (pintype "unspecified"))
    )
    (net (code "58") (name "Net-(U7-OUTD)") (class "Default")
      (node (ref "R30") (pin "1") (pinfunction "1_1") (pintype "unspecified"))
      (node (ref "U47") (pin "3") (pinfunction "3_3") (pintype "unspecified"))
      (node (ref "U7") (pin "14") (pinfunction "OUTD_14") (pintype "unspecified"))
    )
    (net (code "59") (name "Net-(U10-+INA)") (class "Default")
      (node (ref "U10") (pin "3") (pinfunction "+INA_3") (pintype "unspecified"))
      (node (ref "U9") (pin "3") (pinfunction "W1_3") (pintype "unspecified"))
    )
    (net (code "60") (name "Net-(U10-+INB)") (class "Default")
      (node (ref "U10") (pin "5") (pinfunction "+INB_5") (pintype "unspecified"))
      (node (ref "U9") (pin "6") (pinfunction "W3_6") (pintype "unspecified"))
    )
    (net (code "61") (name "Net-(U10-+INC)") (class "Default")
      (node (ref "U10") (pin "10") (pinfunction "+INC_10") (pintype "unspecified"))
      (node (ref "U9") (pin "19") (pinfunction "W4_19") (pintype "unspecified"))
    )
    (net (code "62") (name "Net-(U10-+IND)") (class "Default")
      (node (ref "U10") (pin "12") (pinfunction "+IND_12") (pintype "unspecified"))
      (node (ref "U9") (pin "22") (pinfunction "W2_22") (pintype "unspecified"))
    )
    (net (code "63") (name "Net-(U10--INA)") (class "Default")
      (node (ref "R42") (pin "2") (pinfunction "2_2") (pintype "unspecified"))
      (node (ref "R43") (pin "2") (pinfunction "2_2") (pintype "unspecified"))
      (node (ref "U10") (pin "2") (pinfunction "-INA_2") (pintype "unspecified"))
    )
    (net (code "64") (name "Net-(U10--INB)") (class "Default")
      (node (ref "R40") (pin "2") (pinfunction "2_2") (pintype "unspecified"))
      (node (ref "R41") (pin "1") (pinfunction "1_1") (pintype "unspecified"))
      (node (ref "U10") (pin "6") (pinfunction "-INB_6") (pintype "unspecified"))
    )
    (net (code "65") (name "Net-(U10--INC)") (class "Default")
      (node (ref "R37") (pin "1") (pinfunction "1_1") (pintype "unspecified"))
      (node (ref "R38") (pin "1") (pinfunction "1_1") (pintype "unspecified"))
      (node (ref "U10") (pin "9") (pinfunction "-INC_9") (pintype "unspecified"))
    )
    (net (code "66") (name "Net-(U10--IND)") (class "Default")
      (node (ref "R36") (pin "1") (pinfunction "1_1") (pintype "unspecified"))
      (node (ref "R39") (pin "2") (pinfunction "2_2") (pintype "unspecified"))
      (node (ref "U10") (pin "13") (pinfunction "-IND_13") (pintype "unspecified"))
    )
    (net (code "67") (name "Net-(U10-OUTA)") (class "Default")
      (node (ref "R43") (pin "1") (pinfunction "1_1") (pintype "unspecified"))
      (node (ref "U10") (pin "1") (pinfunction "OUTA_1") (pintype "unspecified"))
      (node (ref "U49") (pin "4") (pinfunction "4_4") (pintype "unspecified"))
    )
    (net (code "68") (name "Net-(U10-OUTB)") (class "Default")
      (node (ref "R41") (pin "2") (pinfunction "2_2") (pintype "unspecified"))
      (node (ref "U10") (pin "7") (pinfunction "OUTB_7") (pintype "unspecified"))
      (node (ref "U49") (pin "2") (pinfunction "2_2") (pintype "unspecified"))
    )
    (net (code "69") (name "Net-(U10-OUTC)") (class "Default")
      (node (ref "R38") (pin "2") (pinfunction "2_2") (pintype "unspecified"))
      (node (ref "U10") (pin "8") (pinfunction "OUTC_8") (pintype "unspecified"))
      (node (ref "U49") (pin "1") (pinfunction "1_1") (pintype "unspecified"))
    )
    (net (code "70") (name "Net-(U10-OUTD)") (class "Default")
      (node (ref "R39") (pin "1") (pinfunction "1_1") (pintype "unspecified"))
      (node (ref "U10") (pin "14") (pinfunction "OUTD_14") (pintype "unspecified"))
      (node (ref "U49") (pin "3") (pinfunction "3_3") (pintype "unspecified"))
    )
    (net (code "71") (name "Net-(U11-+INA)") (class "Default")
      (node (ref "U11") (pin "3") (pinfunction "+INA_3") (pintype "unspecified"))
      (node (ref "U12") (pin "3") (pinfunction "W1_3") (pintype "unspecified"))
    )
    (net (code "72") (name "Net-(U11-+INB)") (class "Default")
      (node (ref "U11") (pin "5") (pinfunction "+INB_5") (pintype "unspecified"))
      (node (ref "U12") (pin "6") (pinfunction "W3_6") (pintype "unspecified"))
    )
    (net (code "73") (name "Net-(U11-+INC)") (class "Default")
      (node (ref "U11") (pin "10") (pinfunction "+INC_10") (pintype "unspecified"))
      (node (ref "U12") (pin "19") (pinfunction "W4_19") (pintype "unspecified"))
    )
    (net (code "74") (name "Net-(U11-+IND)") (class "Default")
      (node (ref "U11") (pin "12") (pinfunction "+IND_12") (pintype "unspecified"))
      (node (ref "U12") (pin "22") (pinfunction "W2_22") (pintype "unspecified"))
    )
    (net (code "75") (name "Net-(U11--INA)") (class "Default")
      (node (ref "R44") (pin "2") (pinfunction "2_2") (pintype "unspecified"))
      (node (ref "R45") (pin "2") (pinfunction "2_2") (pintype "unspecified"))
      (node (ref "U11") (pin "2") (pinfunction "-INA_2") (pintype "unspecified"))
    )
    (net (code "76") (name "Net-(U11--INB)") (class "Default")
      (node (ref "R46") (pin "1") (pinfunction "1_1") (pintype "unspecified"))
      (node (ref "R47") (pin "2") (pinfunction "2_2") (pintype "unspecified"))
      (node (ref "U11") (pin "6") (pinfunction "-INB_6") (pintype "unspecified"))
    )
    (net (code "77") (name "Net-(U11--INC)") (class "Default")
      (node (ref "R49") (pin "1") (pinfunction "1_1") (pintype "unspecified"))
      (node (ref "R50") (pin "1") (pinfunction "1_1") (pintype "unspecified"))
      (node (ref "U11") (pin "9") (pinfunction "-INC_9") (pintype "unspecified"))
    )
    (net (code "78") (name "Net-(U11--IND)") (class "Default")
      (node (ref "R48") (pin "2") (pinfunction "2_2") (pintype "unspecified"))
      (node (ref "R51") (pin "1") (pinfunction "1_1") (pintype "unspecified"))
      (node (ref "U11") (pin "13") (pinfunction "-IND_13") (pintype "unspecified"))
    )
    (net (code "79") (name "Net-(U11-OUTA)") (class "Default")
      (node (ref "R44") (pin "1") (pinfunction "1_1") (pintype "unspecified"))
      (node (ref "U11") (pin "1") (pinfunction "OUTA_1") (pintype "unspecified"))
      (node (ref "U48") (pin "4") (pinfunction "4_4") (pintype "unspecified"))
    )
    (net (code "80") (name "Net-(U11-OUTB)") (class "Default")
      (node (ref "R46") (pin "2") (pinfunction "2_2") (pintype "unspecified"))
      (node (ref "U11") (pin "7") (pinfunction "OUTB_7") (pintype "unspecified"))
      (node (ref "U48") (pin "2") (pinfunction "2_2") (pintype "unspecified"))
    )
    (net (code "81") (name "Net-(U11-OUTC)") (class "Default")
      (node (ref "R49") (pin "2") (pinfunction "2_2") (pintype "unspecified"))
      (node (ref "U11") (pin "8") (pinfunction "OUTC_8") (pintype "unspecified"))
      (node (ref "U48") (pin "1") (pinfunction "1_1") (pintype "unspecified"))
    )
    (net (code "82") (name "Net-(U11-OUTD)") (class "Default")
      (node (ref "R48") (pin "1") (pinfunction "1_1") (pintype "unspecified"))
      (node (ref "U11") (pin "14") (pinfunction "OUTD_14") (pintype "unspecified"))
      (node (ref "U48") (pin "3") (pinfunction "3_3") (pintype "unspecified"))
    )
    (net (code "83") (name "Net-(U12-SDI{slash}SDA)") (class "Default")
      (node (ref "R34") (pin "1") (pinfunction "1_1") (pintype "unspecified"))
      (node (ref "U12") (pin "11") (pinfunction "SDI/SDA_11") (pintype "unspecified"))
      (node (ref "U8") (pin "16") (pinfunction "SDO/O1_16") (pintype "unspecified"))
    )
    (net (code "84") (name "Net-(U12-SDO{slash}O1)") (class "Default")
      (node (ref "R52") (pin "1") (pinfunction "1_1") (pintype "unspecified"))
      (node (ref "U12") (pin "16") (pinfunction "SDO/O1_16") (pintype "unspecified"))
      (node (ref "U9") (pin "11") (pinfunction "SDI/SDA_11") (pintype "unspecified"))
    )
    (net (code "85") (name "Net-(U13-SDI{slash}SDA)") (class "Default")
      (node (ref "R71") (pin "1") (pinfunction "1_1") (pintype "unspecified"))
      (node (ref "U13") (pin "11") (pinfunction "SDI/SDA_11") (pintype "unspecified"))
      (node (ref "U18") (pin "16") (pinfunction "SDO/O1_16") (pintype "unspecified"))
    )
    (net (code "86") (name "Net-(U13-SDO{slash}O1)") (class "Default")
      (node (ref "R53") (pin "1") (pinfunction "1_1") (pintype "unspecified"))
      (node (ref "U13") (pin "16") (pinfunction "SDO/O1_16") (pintype "unspecified"))
      (node (ref "U17") (pin "11") (pinfunction "SDI/SDA_11") (pintype "unspecified"))
    )
    (net (code "87") (name "Net-(U13-W1)") (class "Default")
      (node (ref "U13") (pin "3") (pinfunction "W1_3") (pintype "unspecified"))
      (node (ref "U14") (pin "3") (pinfunction "+INA_3") (pintype "unspecified"))
    )
    (net (code "88") (name "Net-(U13-W2)") (class "Default")
      (node (ref "U13") (pin "22") (pinfunction "W2_22") (pintype "unspecified"))
      (node (ref "U14") (pin "12") (pinfunction "+IND_12") (pintype "unspecified"))
    )
    (net (code "89") (name "Net-(U13-W3)") (class "Default")
      (node (ref "U13") (pin "6") (pinfunction "W3_6") (pintype "unspecified"))
      (node (ref "U14") (pin "5") (pinfunction "+INB_5") (pintype "unspecified"))
    )
    (net (code "90") (name "Net-(U13-W4)") (class "Default")
      (node (ref "U13") (pin "19") (pinfunction "W4_19") (pintype "unspecified"))
      (node (ref "U14") (pin "10") (pinfunction "+INC_10") (pintype "unspecified"))
    )
    (net (code "91") (name "Net-(U14--INA)") (class "Default")
      (node (ref "R60") (pin "2") (pinfunction "2_2") (pintype "unspecified"))
      (node (ref "R61") (pin "2") (pinfunction "2_2") (pintype "unspecified"))
      (node (ref "U14") (pin "2") (pinfunction "-INA_2") (pintype "unspecified"))
    )
    (net (code "92") (name "Net-(U14--INB)") (class "Default")
      (node (ref "R58") (pin "2") (pinfunction "2_2") (pintype "unspecified"))
      (node (ref "R59") (pin "1") (pinfunction "1_1") (pintype "unspecified"))
      (node (ref "U14") (pin "6") (pinfunction "-INB_6") (pintype "unspecified"))
    )
    (net (code "93") (name "Net-(U14--INC)") (class "Default")
      (node (ref "R55") (pin "1") (pinfunction "1_1") (pintype "unspecified"))
      (node (ref "R56") (pin "1") (pinfunction "1_1") (pintype "unspecified"))
      (node (ref "U14") (pin "9") (pinfunction "-INC_9") (pintype "unspecified"))
    )
    (net (code "94") (name "Net-(U14--IND)") (class "Default")
      (node (ref "R54") (pin "1") (pinfunction "1_1") (pintype "unspecified"))
      (node (ref "R57") (pin "2") (pinfunction "2_2") (pintype "unspecified"))
      (node (ref "U14") (pin "13") (pinfunction "-IND_13") (pintype "unspecified"))
    )
    (net (code "95") (name "Net-(U14-OUTA)") (class "Default")
      (node (ref "R61") (pin "1") (pinfunction "1_1") (pintype "unspecified"))
      (node (ref "U14") (pin "1") (pinfunction "OUTA_1") (pintype "unspecified"))
      (node (ref "U52") (pin "4") (pinfunction "4_4") (pintype "unspecified"))
    )
    (net (code "96") (name "Net-(U14-OUTB)") (class "Default")
      (node (ref "R59") (pin "2") (pinfunction "2_2") (pintype "unspecified"))
      (node (ref "U14") (pin "7") (pinfunction "OUTB_7") (pintype "unspecified"))
      (node (ref "U52") (pin "2") (pinfunction "2_2") (pintype "unspecified"))
    )
    (net (code "97") (name "Net-(U14-OUTC)") (class "Default")
      (node (ref "R56") (pin "2") (pinfunction "2_2") (pintype "unspecified"))
      (node (ref "U14") (pin "8") (pinfunction "OUTC_8") (pintype "unspecified"))
      (node (ref "U52") (pin "1") (pinfunction "1_1") (pintype "unspecified"))
    )
    (net (code "98") (name "Net-(U14-OUTD)") (class "Default")
      (node (ref "R57") (pin "1") (pinfunction "1_1") (pintype "unspecified"))
      (node (ref "U14") (pin "14") (pinfunction "OUTD_14") (pintype "unspecified"))
      (node (ref "U52") (pin "3") (pinfunction "3_3") (pintype "unspecified"))
    )
    (net (code "99") (name "Net-(U15-PG1)") (class "Default")
      (node (ref "R28") (pin "1") (pinfunction "1_1") (pintype "unspecified"))
      (node (ref "U15") (pin "1") (pinfunction "PG1_1") (pintype "unspecified"))
      (node (ref "U4") (pin "D6") (pinfunction "PG1_D6") (pintype "unspecified"))
    )
    (net (code "100") (name "Net-(U15-PG2)") (class "Default")
      (node (ref "R27") (pin "2") (pinfunction "2_2") (pintype "unspecified"))
      (node (ref "U15") (pin "2") (pinfunction "PG2_2") (pintype "unspecified"))
      (node (ref "U4") (pin "H6") (pinfunction "PG2_H6") (pintype "unspecified"))
    )
    (net (code "101") (name "Net-(U16-+INA)") (class "Default")
      (node (ref "U16") (pin "3") (pinfunction "+INA_3") (pintype "unspecified"))
      (node (ref "U17") (pin "3") (pinfunction "W1_3") (pintype "unspecified"))
    )
    (net (code "102") (name "Net-(U16-+INB)") (class "Default")
      (node (ref "U16") (pin "5") (pinfunction "+INB_5") (pintype "unspecified"))
      (node (ref "U17") (pin "6") (pinfunction "W3_6") (pintype "unspecified"))
    )
    (net (code "103") (name "Net-(U16-+INC)") (class "Default")
      (node (ref "U16") (pin "10") (pinfunction "+INC_10") (pintype "unspecified"))
      (node (ref "U17") (pin "19") (pinfunction "W4_19") (pintype "unspecified"))
    )
    (net (code "104") (name "Net-(U16-+IND)") (class "Default")
      (node (ref "U16") (pin "12") (pinfunction "+IND_12") (pintype "unspecified"))
      (node (ref "U17") (pin "22") (pinfunction "W2_22") (pintype "unspecified"))
    )
    (net (code "105") (name "Net-(U16--INA)") (class "Default")
      (node (ref "R62") (pin "2") (pinfunction "2_2") (pintype "unspecified"))
      (node (ref "R63") (pin "2") (pinfunction "2_2") (pintype "unspecified"))
      (node (ref "U16") (pin "2") (pinfunction "-INA_2") (pintype "unspecified"))
    )
    (net (code "106") (name "Net-(U16--INB)") (class "Default")
      (node (ref "R64") (pin "1") (pinfunction "1_1") (pintype "unspecified"))
      (node (ref "R65") (pin "2") (pinfunction "2_2") (pintype "unspecified"))
      (node (ref "U16") (pin "6") (pinfunction "-INB_6") (pintype "unspecified"))
    )
    (net (code "107") (name "Net-(U16--INC)") (class "Default")
      (node (ref "R67") (pin "1") (pinfunction "1_1") (pintype "unspecified"))
      (node (ref "R68") (pin "1") (pinfunction "1_1") (pintype "unspecified"))
      (node (ref "U16") (pin "9") (pinfunction "-INC_9") (pintype "unspecified"))
    )
    (net (code "108") (name "Net-(U16--IND)") (class "Default")
      (node (ref "R66") (pin "2") (pinfunction "2_2") (pintype "unspecified"))
      (node (ref "R69") (pin "1") (pinfunction "1_1") (pintype "unspecified"))
      (node (ref "U16") (pin "13") (pinfunction "-IND_13") (pintype "unspecified"))
    )
    (net (code "109") (name "Net-(U16-OUTA)") (class "Default")
      (node (ref "R62") (pin "1") (pinfunction "1_1") (pintype "unspecified"))
      (node (ref "U16") (pin "1") (pinfunction "OUTA_1") (pintype "unspecified"))
      (node (ref "U53") (pin "4") (pinfunction "4_4") (pintype "unspecified"))
    )
    (net (code "110") (name "Net-(U16-OUTB)") (class "Default")
      (node (ref "R64") (pin "2") (pinfunction "2_2") (pintype "unspecified"))
      (node (ref "U16") (pin "7") (pinfunction "OUTB_7") (pintype "unspecified"))
      (node (ref "U53") (pin "2") (pinfunction "2_2") (pintype "unspecified"))
    )
    (net (code "111") (name "Net-(U16-OUTC)") (class "Default")
      (node (ref "R67") (pin "2") (pinfunction "2_2") (pintype "unspecified"))
      (node (ref "U16") (pin "8") (pinfunction "OUTC_8") (pintype "unspecified"))
      (node (ref "U53") (pin "1") (pinfunction "1_1") (pintype "unspecified"))
    )
    (net (code "112") (name "Net-(U16-OUTD)") (class "Default")
      (node (ref "R66") (pin "1") (pinfunction "1_1") (pintype "unspecified"))
      (node (ref "U16") (pin "14") (pinfunction "OUTD_14") (pintype "unspecified"))
      (node (ref "U53") (pin "3") (pinfunction "3_3") (pintype "unspecified"))
    )
    (net (code "113") (name "Net-(U17-SDO{slash}O1)") (class "Default")
      (node (ref "R70") (pin "1") (pinfunction "1_1") (pintype "unspecified"))
      (node (ref "U17") (pin "16") (pinfunction "SDO/O1_16") (pintype "unspecified"))
      (node (ref "U30") (pin "11") (pinfunction "SDI/SDA_11") (pintype "unspecified"))
    )
    (net (code "114") (name "Net-(U18-SDI{slash}SDA)") (class "Default")
      (node (ref "R88") (pin "1") (pinfunction "1_1") (pintype "unspecified"))
      (node (ref "U18") (pin "11") (pinfunction "SDI/SDA_11") (pintype "unspecified"))
      (node (ref "U21") (pin "16") (pinfunction "SDO/O1_16") (pintype "unspecified"))
    )
    (net (code "115") (name "Net-(U18-W1)") (class "Default")
      (node (ref "U18") (pin "3") (pinfunction "W1_3") (pintype "unspecified"))
      (node (ref "U19") (pin "3") (pinfunction "+INA_3") (pintype "unspecified"))
    )
    (net (code "116") (name "Net-(U18-W2)") (class "Default")
      (node (ref "U18") (pin "22") (pinfunction "W2_22") (pintype "unspecified"))
      (node (ref "U19") (pin "12") (pinfunction "+IND_12") (pintype "unspecified"))
    )
    (net (code "117") (name "Net-(U18-W3)") (class "Default")
      (node (ref "U18") (pin "6") (pinfunction "W3_6") (pintype "unspecified"))
      (node (ref "U19") (pin "5") (pinfunction "+INB_5") (pintype "unspecified"))
    )
    (net (code "118") (name "Net-(U18-W4)") (class "Default")
      (node (ref "U18") (pin "19") (pinfunction "W4_19") (pintype "unspecified"))
      (node (ref "U19") (pin "10") (pinfunction "+INC_10") (pintype "unspecified"))
    )
    (net (code "119") (name "Net-(U19--INA)") (class "Default")
      (node (ref "R78") (pin "2") (pinfunction "2_2") (pintype "unspecified"))
      (node (ref "R79") (pin "2") (pinfunction "2_2") (pintype "unspecified"))
      (node (ref "U19") (pin "2") (pinfunction "-INA_2") (pintype "unspecified"))
    )
    (net (code "120") (name "Net-(U19--INB)") (class "Default")
      (node (ref "R76") (pin "2") (pinfunction "2_2") (pintype "unspecified"))
      (node (ref "R77") (pin "1") (pinfunction "1_1") (pintype "unspecified"))
      (node (ref "U19") (pin "6") (pinfunction "-INB_6") (pintype "unspecified"))
    )
    (net (code "121") (name "Net-(U19--INC)") (class "Default")
      (node (ref "R73") (pin "1") (pinfunction "1_1") (pintype "unspecified"))
      (node (ref "R74") (pin "1") (pinfunction "1_1") (pintype "unspecified"))
      (node (ref "U19") (pin "9") (pinfunction "-INC_9") (pintype "unspecified"))
    )
    (net (code "122") (name "Net-(U19--IND)") (class "Default")
      (node (ref "R72") (pin "1") (pinfunction "1_1") (pintype "unspecified"))
      (node (ref "R75") (pin "2") (pinfunction "2_2") (pintype "unspecified"))
      (node (ref "U19") (pin "13") (pinfunction "-IND_13") (pintype "unspecified"))
    )
    (net (code "123") (name "Net-(U19-OUTA)") (class "Default")
      (node (ref "R79") (pin "1") (pinfunction "1_1") (pintype "unspecified"))
      (node (ref "U19") (pin "1") (pinfunction "OUTA_1") (pintype "unspecified"))
      (node (ref "U51") (pin "4") (pinfunction "4_4") (pintype "unspecified"))
    )
    (net (code "124") (name "Net-(U19-OUTB)") (class "Default")
      (node (ref "R77") (pin "2") (pinfunction "2_2") (pintype "unspecified"))
      (node (ref "U19") (pin "7") (pinfunction "OUTB_7") (pintype "unspecified"))
      (node (ref "U51") (pin "2") (pinfunction "2_2") (pintype "unspecified"))
    )
    (net (code "125") (name "Net-(U19-OUTC)") (class "Default")
      (node (ref "R74") (pin "2") (pinfunction "2_2") (pintype "unspecified"))
      (node (ref "U19") (pin "8") (pinfunction "OUTC_8") (pintype "unspecified"))
      (node (ref "U51") (pin "1") (pinfunction "1_1") (pintype "unspecified"))
    )
    (net (code "126") (name "Net-(U19-OUTD)") (class "Default")
      (node (ref "R75") (pin "1") (pinfunction "1_1") (pintype "unspecified"))
      (node (ref "U19") (pin "14") (pinfunction "OUTD_14") (pintype "unspecified"))
      (node (ref "U51") (pin "3") (pinfunction "3_3") (pintype "unspecified"))
    )
    (net (code "127") (name "Net-(U20-+INA)") (class "Default")
      (node (ref "U20") (pin "3") (pinfunction "+INA_3") (pintype "unspecified"))
      (node (ref "U21") (pin "3") (pinfunction "W1_3") (pintype "unspecified"))
    )
    (net (code "128") (name "Net-(U20-+INB)") (class "Default")
      (node (ref "U20") (pin "5") (pinfunction "+INB_5") (pintype "unspecified"))
      (node (ref "U21") (pin "6") (pinfunction "W3_6") (pintype "unspecified"))
    )
    (net (code "129") (name "Net-(U20-+INC)") (class "Default")
      (node (ref "U20") (pin "10") (pinfunction "+INC_10") (pintype "unspecified"))
      (node (ref "U21") (pin "19") (pinfunction "W4_19") (pintype "unspecified"))
    )
    (net (code "130") (name "Net-(U20-+IND)") (class "Default")
      (node (ref "U20") (pin "12") (pinfunction "+IND_12") (pintype "unspecified"))
      (node (ref "U21") (pin "22") (pinfunction "W2_22") (pintype "unspecified"))
    )
    (net (code "131") (name "Net-(U20--INA)") (class "Default")
      (node (ref "R80") (pin "2") (pinfunction "2_2") (pintype "unspecified"))
      (node (ref "R81") (pin "2") (pinfunction "2_2") (pintype "unspecified"))
      (node (ref "U20") (pin "2") (pinfunction "-INA_2") (pintype "unspecified"))
    )
    (net (code "132") (name "Net-(U20--INB)") (class "Default")
      (node (ref "R82") (pin "1") (pinfunction "1_1") (pintype "unspecified"))
      (node (ref "R83") (pin "2") (pinfunction "2_2") (pintype "unspecified"))
      (node (ref "U20") (pin "6") (pinfunction "-INB_6") (pintype "unspecified"))
    )
    (net (code "133") (name "Net-(U20--INC)") (class "Default")
      (node (ref "R85") (pin "1") (pinfunction "1_1") (pintype "unspecified"))
      (node (ref "R86") (pin "1") (pinfunction "1_1") (pintype "unspecified"))
      (node (ref "U20") (pin "9") (pinfunction "-INC_9") (pintype "unspecified"))
    )
    (net (code "134") (name "Net-(U20--IND)") (class "Default")
      (node (ref "R84") (pin "2") (pinfunction "2_2") (pintype "unspecified"))
      (node (ref "R87") (pin "1") (pinfunction "1_1") (pintype "unspecified"))
      (node (ref "U20") (pin "13") (pinfunction "-IND_13") (pintype "unspecified"))
    )
    (net (code "135") (name "Net-(U20-OUTA)") (class "Default")
      (node (ref "R80") (pin "1") (pinfunction "1_1") (pintype "unspecified"))
      (node (ref "U20") (pin "1") (pinfunction "OUTA_1") (pintype "unspecified"))
      (node (ref "U50") (pin "4") (pinfunction "4_4") (pintype "unspecified"))
    )
    (net (code "136") (name "Net-(U20-OUTB)") (class "Default")
      (node (ref "R82") (pin "2") (pinfunction "2_2") (pintype "unspecified"))
      (node (ref "U20") (pin "7") (pinfunction "OUTB_7") (pintype "unspecified"))
      (node (ref "U50") (pin "2") (pinfunction "2_2") (pintype "unspecified"))
    )
    (net (code "137") (name "Net-(U20-OUTC)") (class "Default")
      (node (ref "R85") (pin "2") (pinfunction "2_2") (pintype "unspecified"))
      (node (ref "U20") (pin "8") (pinfunction "OUTC_8") (pintype "unspecified"))
      (node (ref "U50") (pin "1") (pinfunction "1_1") (pintype "unspecified"))
    )
    (net (code "138") (name "Net-(U20-OUTD)") (class "Default")
      (node (ref "R84") (pin "1") (pinfunction "1_1") (pintype "unspecified"))
      (node (ref "U20") (pin "14") (pinfunction "OUTD_14") (pintype "unspecified"))
      (node (ref "U50") (pin "3") (pinfunction "3_3") (pintype "unspecified"))
    )
    (net (code "139") (name "Net-(U21-SDI{slash}SDA)") (class "Default")
      (node (ref "R35") (pin "1") (pinfunction "1_1") (pintype "unspecified"))
      (node (ref "U21") (pin "11") (pinfunction "SDI/SDA_11") (pintype "unspecified"))
      (node (ref "U9") (pin "16") (pinfunction "SDO/O1_16") (pintype "unspecified"))
    )
    (net (code "140") (name "Net-(U22-SDI{slash}SDA)") (class "Default")
      (node (ref "R107") (pin "1") (pinfunction "1_1") (pintype "unspecified"))
      (node (ref "U22") (pin "11") (pinfunction "SDI/SDA_11") (pintype "unspecified"))
      (node (ref "U27") (pin "16") (pinfunction "SDO/O1_16") (pintype "unspecified"))
    )
    (net (code "141") (name "Net-(U22-SDO{slash}O1)") (class "Default")
      (node (ref "R26") (pin "1") (pinfunction "1_1") (pintype "unspecified"))
      (node (ref "U22") (pin "16") (pinfunction "SDO/O1_16") (pintype "unspecified"))
      (node (ref "U26") (pin "11") (pinfunction "SDI/SDA_11") (pintype "unspecified"))
    )
    (net (code "142") (name "Net-(U22-W1)") (class "Default")
      (node (ref "U22") (pin "3") (pinfunction "W1_3") (pintype "unspecified"))
      (node (ref "U23") (pin "3") (pinfunction "+INA_3") (pintype "unspecified"))
    )
    (net (code "143") (name "Net-(U22-W2)") (class "Default")
      (node (ref "U22") (pin "22") (pinfunction "W2_22") (pintype "unspecified"))
      (node (ref "U23") (pin "12") (pinfunction "+IND_12") (pintype "unspecified"))
    )
    (net (code "144") (name "Net-(U22-W3)") (class "Default")
      (node (ref "U22") (pin "6") (pinfunction "W3_6") (pintype "unspecified"))
      (node (ref "U23") (pin "5") (pinfunction "+INB_5") (pintype "unspecified"))
    )
    (net (code "145") (name "Net-(U22-W4)") (class "Default")
      (node (ref "U22") (pin "19") (pinfunction "W4_19") (pintype "unspecified"))
      (node (ref "U23") (pin "10") (pinfunction "+INC_10") (pintype "unspecified"))
    )
    (net (code "146") (name "Net-(U23--INA)") (class "Default")
      (node (ref "R96") (pin "2") (pinfunction "2_2") (pintype "unspecified"))
      (node (ref "R97") (pin "2") (pinfunction "2_2") (pintype "unspecified"))
      (node (ref "U23") (pin "2") (pinfunction "-INA_2") (pintype "unspecified"))
    )
    (net (code "147") (name "Net-(U23--INB)") (class "Default")
      (node (ref "R94") (pin "2") (pinfunction "2_2") (pintype "unspecified"))
      (node (ref "R95") (pin "1") (pinfunction "1_1") (pintype "unspecified"))
      (node (ref "U23") (pin "6") (pinfunction "-INB_6") (pintype "unspecified"))
    )
    (net (code "148") (name "Net-(U23--INC)") (class "Default")
      (node (ref "R91") (pin "1") (pinfunction "1_1") (pintype "unspecified"))
      (node (ref "R92") (pin "1") (pinfunction "1_1") (pintype "unspecified"))
      (node (ref "U23") (pin "9") (pinfunction "-INC_9") (pintype "unspecified"))
    )
    (net (code "149") (name "Net-(U23--IND)") (class "Default")
      (node (ref "R90") (pin "1") (pinfunction "1_1") (pintype "unspecified"))
      (node (ref "R93") (pin "2") (pinfunction "2_2") (pintype "unspecified"))
      (node (ref "U23") (pin "13") (pinfunction "-IND_13") (pintype "unspecified"))
    )
    (net (code "150") (name "Net-(U23-OUTA)") (class "Default")
      (node (ref "R97") (pin "1") (pinfunction "1_1") (pintype "unspecified"))
      (node (ref "U23") (pin "1") (pinfunction "OUTA_1") (pintype "unspecified"))
      (node (ref "U56") (pin "4") (pinfunction "4_4") (pintype "unspecified"))
    )
    (net (code "151") (name "Net-(U23-OUTB)") (class "Default")
      (node (ref "R95") (pin "2") (pinfunction "2_2") (pintype "unspecified"))
      (node (ref "U23") (pin "7") (pinfunction "OUTB_7") (pintype "unspecified"))
      (node (ref "U56") (pin "2") (pinfunction "2_2") (pintype "unspecified"))
    )
    (net (code "152") (name "Net-(U23-OUTC)") (class "Default")
      (node (ref "R92") (pin "2") (pinfunction "2_2") (pintype "unspecified"))
      (node (ref "U23") (pin "8") (pinfunction "OUTC_8") (pintype "unspecified"))
      (node (ref "U56") (pin "1") (pinfunction "1_1") (pintype "unspecified"))
    )
    (net (code "153") (name "Net-(U23-OUTD)") (class "Default")
      (node (ref "R93") (pin "1") (pinfunction "1_1") (pintype "unspecified"))
      (node (ref "U23") (pin "14") (pinfunction "OUTD_14") (pintype "unspecified"))
      (node (ref "U56") (pin "3") (pinfunction "3_3") (pintype "unspecified"))
    )
    (net (code "154") (name "Net-(U24-+INA)") (class "Default")
      (node (ref "U24") (pin "3") (pinfunction "+INA_3") (pintype "unspecified"))
      (node (ref "U26") (pin "3") (pinfunction "W1_3") (pintype "unspecified"))
    )
    (net (code "155") (name "Net-(U24-+INB)") (class "Default")
      (node (ref "U24") (pin "5") (pinfunction "+INB_5") (pintype "unspecified"))
      (node (ref "U26") (pin "6") (pinfunction "W3_6") (pintype "unspecified"))
    )
    (net (code "156") (name "Net-(U24-+INC)") (class "Default")
      (node (ref "U24") (pin "10") (pinfunction "+INC_10") (pintype "unspecified"))
      (node (ref "U26") (pin "19") (pinfunction "W4_19") (pintype "unspecified"))
    )
    (net (code "157") (name "Net-(U24-+IND)") (class "Default")
      (node (ref "U24") (pin "12") (pinfunction "+IND_12") (pintype "unspecified"))
      (node (ref "U26") (pin "22") (pinfunction "W2_22") (pintype "unspecified"))
    )
    (net (code "158") (name "Net-(U24--INA)") (class "Default")
      (node (ref "R98") (pin "2") (pinfunction "2_2") (pintype "unspecified"))
      (node (ref "R99") (pin "2") (pinfunction "2_2") (pintype "unspecified"))
      (node (ref "U24") (pin "2") (pinfunction "-INA_2") (pintype "unspecified"))
    )
    (net (code "159") (name "Net-(U24--INB)") (class "Default")
      (node (ref "R100") (pin "1") (pinfunction "1_1") (pintype "unspecified"))
      (node (ref "R101") (pin "2") (pinfunction "2_2") (pintype "unspecified"))
      (node (ref "U24") (pin "6") (pinfunction "-INB_6") (pintype "unspecified"))
    )
    (net (code "160") (name "Net-(U24--INC)") (class "Default")
      (node (ref "R103") (pin "1") (pinfunction "1_1") (pintype "unspecified"))
      (node (ref "R104") (pin "1") (pinfunction "1_1") (pintype "unspecified"))
      (node (ref "U24") (pin "9") (pinfunction "-INC_9") (pintype "unspecified"))
    )
    (net (code "161") (name "Net-(U24--IND)") (class "Default")
      (node (ref "R102") (pin "2") (pinfunction "2_2") (pintype "unspecified"))
      (node (ref "R105") (pin "1") (pinfunction "1_1") (pintype "unspecified"))
      (node (ref "U24") (pin "13") (pinfunction "-IND_13") (pintype "unspecified"))
    )
    (net (code "162") (name "Net-(U24-OUTA)") (class "Default")
      (node (ref "R98") (pin "1") (pinfunction "1_1") (pintype "unspecified"))
      (node (ref "U24") (pin "1") (pinfunction "OUTA_1") (pintype "unspecified"))
      (node (ref "U57") (pin "4") (pinfunction "4_4") (pintype "unspecified"))
    )
    (net (code "163") (name "Net-(U24-OUTB)") (class "Default")
      (node (ref "R100") (pin "2") (pinfunction "2_2") (pintype "unspecified"))
      (node (ref "U24") (pin "7") (pinfunction "OUTB_7") (pintype "unspecified"))
      (node (ref "U57") (pin "2") (pinfunction "2_2") (pintype "unspecified"))
    )
    (net (code "164") (name "Net-(U24-OUTC)") (class "Default")
      (node (ref "R103") (pin "2") (pinfunction "2_2") (pintype "unspecified"))
      (node (ref "U24") (pin "8") (pinfunction "OUTC_8") (pintype "unspecified"))
      (node (ref "U57") (pin "1") (pinfunction "1_1") (pintype "unspecified"))
    )
    (net (code "165") (name "Net-(U24-OUTD)") (class "Default")
      (node (ref "R102") (pin "1") (pinfunction "1_1") (pintype "unspecified"))
      (node (ref "U24") (pin "14") (pinfunction "OUTD_14") (pintype "unspecified"))
      (node (ref "U57") (pin "3") (pinfunction "3_3") (pintype "unspecified"))
    )
    (net (code "166") (name "Net-(U25-CONT)") (class "Default")
      (node (ref "C2") (pin "1") (pinfunction "1_1") (pintype "unspecified"))
      (node (ref "U25") (pin "5") (pinfunction "CONT_5") (pintype "unspecified"))
    )
    (net (code "167") (name "Net-(U25-DISCH)") (class "Default")
      (node (ref "R129") (pin "2") (pinfunction "2_2") (pintype "unspecified"))
      (node (ref "U25") (pin "7") (pinfunction "DISCH_7") (pintype "unspecified"))
    )
    (net (code "168") (name "Net-(U25-THRES)") (class "Default")
      (node (ref "C1") (pin "1") (pinfunction "1_1") (pintype "unspecified"))
      (node (ref "R130") (pin "2") (pinfunction "2_2") (pintype "unspecified"))
      (node (ref "U25") (pin "2") (pinfunction "TRIG_2") (pintype "unspecified"))
      (node (ref "U25") (pin "6") (pinfunction "THRES_6") (pintype "unspecified"))
    )
    (net (code "169") (name "Net-(U26-SDO{slash}O1)") (class "Default")
      (node (ref "R106") (pin "1") (pinfunction "1_1") (pintype "unspecified"))
      (node (ref "U26") (pin "16") (pinfunction "SDO/O1_16") (pintype "unspecified"))
      (node (ref "U32") (pin "11") (pinfunction "SDI/SDA_11") (pintype "unspecified"))
    )
    (net (code "170") (name "Net-(U27-SDI{slash}SDA)") (class "Default")
      (node (ref "R89") (pin "1") (pinfunction "1_1") (pintype "unspecified"))
      (node (ref "U27") (pin "11") (pinfunction "SDI/SDA_11") (pintype "unspecified"))
      (node (ref "U30") (pin "16") (pinfunction "SDO/O1_16") (pintype "unspecified"))
    )
    (net (code "171") (name "Net-(U27-W1)") (class "Default")
      (node (ref "U27") (pin "3") (pinfunction "W1_3") (pintype "unspecified"))
      (node (ref "U28") (pin "3") (pinfunction "+INA_3") (pintype "unspecified"))
    )
    (net (code "172") (name "Net-(U27-W2)") (class "Default")
      (node (ref "U27") (pin "22") (pinfunction "W2_22") (pintype "unspecified"))
      (node (ref "U28") (pin "12") (pinfunction "+IND_12") (pintype "unspecified"))
    )
    (net (code "173") (name "Net-(U27-W3)") (class "Default")
      (node (ref "U27") (pin "6") (pinfunction "W3_6") (pintype "unspecified"))
      (node (ref "U28") (pin "5") (pinfunction "+INB_5") (pintype "unspecified"))
    )
    (net (code "174") (name "Net-(U27-W4)") (class "Default")
      (node (ref "U27") (pin "19") (pinfunction "W4_19") (pintype "unspecified"))
      (node (ref "U28") (pin "10") (pinfunction "+INC_10") (pintype "unspecified"))
    )
    (net (code "175") (name "Net-(U28--INA)") (class "Default")
      (node (ref "R114") (pin "2") (pinfunction "2_2") (pintype "unspecified"))
      (node (ref "R115") (pin "2") (pinfunction "2_2") (pintype "unspecified"))
      (node (ref "U28") (pin "2") (pinfunction "-INA_2") (pintype "unspecified"))
    )
    (net (code "176") (name "Net-(U28--INB)") (class "Default")
      (node (ref "R112") (pin "2") (pinfunction "2_2") (pintype "unspecified"))
      (node (ref "R113") (pin "1") (pinfunction "1_1") (pintype "unspecified"))
      (node (ref "U28") (pin "6") (pinfunction "-INB_6") (pintype "unspecified"))
    )
    (net (code "177") (name "Net-(U28--INC)") (class "Default")
      (node (ref "R109") (pin "1") (pinfunction "1_1") (pintype "unspecified"))
      (node (ref "R110") (pin "1") (pinfunction "1_1") (pintype "unspecified"))
      (node (ref "U28") (pin "9") (pinfunction "-INC_9") (pintype "unspecified"))
    )
    (net (code "178") (name "Net-(U28--IND)") (class "Default")
      (node (ref "R108") (pin "1") (pinfunction "1_1") (pintype "unspecified"))
      (node (ref "R111") (pin "2") (pinfunction "2_2") (pintype "unspecified"))
      (node (ref "U28") (pin "13") (pinfunction "-IND_13") (pintype "unspecified"))
    )
    (net (code "179") (name "Net-(U28-OUTA)") (class "Default")
      (node (ref "R115") (pin "1") (pinfunction "1_1") (pintype "unspecified"))
      (node (ref "U28") (pin "1") (pinfunction "OUTA_1") (pintype "unspecified"))
      (node (ref "U55") (pin "4") (pinfunction "4_4") (pintype "unspecified"))
    )
    (net (code "180") (name "Net-(U28-OUTB)") (class "Default")
      (node (ref "R113") (pin "2") (pinfunction "2_2") (pintype "unspecified"))
      (node (ref "U28") (pin "7") (pinfunction "OUTB_7") (pintype "unspecified"))
      (node (ref "U55") (pin "2") (pinfunction "2_2") (pintype "unspecified"))
    )
    (net (code "181") (name "Net-(U28-OUTC)") (class "Default")
      (node (ref "R110") (pin "2") (pinfunction "2_2") (pintype "unspecified"))
      (node (ref "U28") (pin "8") (pinfunction "OUTC_8") (pintype "unspecified"))
      (node (ref "U55") (pin "1") (pinfunction "1_1") (pintype "unspecified"))
    )
    (net (code "182") (name "Net-(U28-OUTD)") (class "Default")
      (node (ref "R111") (pin "1") (pinfunction "1_1") (pintype "unspecified"))
      (node (ref "U28") (pin "14") (pinfunction "OUTD_14") (pintype "unspecified"))
      (node (ref "U55") (pin "3") (pinfunction "3_3") (pintype "unspecified"))
    )
    (net (code "183") (name "Net-(U29-+INA)") (class "Default")
      (node (ref "U29") (pin "3") (pinfunction "+INA_3") (pintype "unspecified"))
      (node (ref "U30") (pin "3") (pinfunction "W1_3") (pintype "unspecified"))
    )
    (net (code "184") (name "Net-(U29-+INB)") (class "Default")
      (node (ref "U29") (pin "5") (pinfunction "+INB_5") (pintype "unspecified"))
      (node (ref "U30") (pin "6") (pinfunction "W3_6") (pintype "unspecified"))
    )
    (net (code "185") (name "Net-(U29-+INC)") (class "Default")
      (node (ref "U29") (pin "10") (pinfunction "+INC_10") (pintype "unspecified"))
      (node (ref "U30") (pin "19") (pinfunction "W4_19") (pintype "unspecified"))
    )
    (net (code "186") (name "Net-(U29-+IND)") (class "Default")
      (node (ref "U29") (pin "12") (pinfunction "+IND_12") (pintype "unspecified"))
      (node (ref "U30") (pin "22") (pinfunction "W2_22") (pintype "unspecified"))
    )
    (net (code "187") (name "Net-(U29--INA)") (class "Default")
      (node (ref "R116") (pin "2") (pinfunction "2_2") (pintype "unspecified"))
      (node (ref "R117") (pin "2") (pinfunction "2_2") (pintype "unspecified"))
      (node (ref "U29") (pin "2") (pinfunction "-INA_2") (pintype "unspecified"))
    )
    (net (code "188") (name "Net-(U29--INB)") (class "Default")
      (node (ref "R118") (pin "1") (pinfunction "1_1") (pintype "unspecified"))
      (node (ref "R119") (pin "2") (pinfunction "2_2") (pintype "unspecified"))
      (node (ref "U29") (pin "6") (pinfunction "-INB_6") (pintype "unspecified"))
    )
    (net (code "189") (name "Net-(U29--INC)") (class "Default")
      (node (ref "R121") (pin "1") (pinfunction "1_1") (pintype "unspecified"))
      (node (ref "R122") (pin "1") (pinfunction "1_1") (pintype "unspecified"))
      (node (ref "U29") (pin "9") (pinfunction "-INC_9") (pintype "unspecified"))
    )
    (net (code "190") (name "Net-(U29--IND)") (class "Default")
      (node (ref "R120") (pin "2") (pinfunction "2_2") (pintype "unspecified"))
      (node (ref "R123") (pin "1") (pinfunction "1_1") (pintype "unspecified"))
      (node (ref "U29") (pin "13") (pinfunction "-IND_13") (pintype "unspecified"))
    )
    (net (code "191") (name "Net-(U29-OUTA)") (class "Default")
      (node (ref "R116") (pin "1") (pinfunction "1_1") (pintype "unspecified"))
      (node (ref "U29") (pin "1") (pinfunction "OUTA_1") (pintype "unspecified"))
      (node (ref "U54") (pin "4") (pinfunction "4_4") (pintype "unspecified"))
    )
    (net (code "192") (name "Net-(U29-OUTB)") (class "Default")
      (node (ref "R118") (pin "2") (pinfunction "2_2") (pintype "unspecified"))
      (node (ref "U29") (pin "7") (pinfunction "OUTB_7") (pintype "unspecified"))
      (node (ref "U54") (pin "2") (pinfunction "2_2") (pintype "unspecified"))
    )
    (net (code "193") (name "Net-(U29-OUTC)") (class "Default")
      (node (ref "R121") (pin "2") (pinfunction "2_2") (pintype "unspecified"))
      (node (ref "U29") (pin "8") (pinfunction "OUTC_8") (pintype "unspecified"))
      (node (ref "U54") (pin "1") (pinfunction "1_1") (pintype "unspecified"))
    )
    (net (code "194") (name "Net-(U29-OUTD)") (class "Default")
      (node (ref "R120") (pin "1") (pinfunction "1_1") (pintype "unspecified"))
      (node (ref "U29") (pin "14") (pinfunction "OUTD_14") (pintype "unspecified"))
      (node (ref "U54") (pin "3") (pinfunction "3_3") (pintype "unspecified"))
    )
    (net (code "195") (name "Net-(U31-+INA)") (class "Default")
      (node (ref "U31") (pin "3") (pinfunction "+INA_3") (pintype "unspecified"))
      (node (ref "U32") (pin "3") (pinfunction "W1_3") (pintype "unspecified"))
    )
    (net (code "196") (name "Net-(U31-+INB)") (class "Default")
      (node (ref "U31") (pin "5") (pinfunction "+INB_5") (pintype "unspecified"))
      (node (ref "U32") (pin "6") (pinfunction "W3_6") (pintype "unspecified"))
    )
    (net (code "197") (name "Net-(U31-+INC)") (class "Default")
      (node (ref "U31") (pin "10") (pinfunction "+INC_10") (pintype "unspecified"))
      (node (ref "U32") (pin "19") (pinfunction "W4_19") (pintype "unspecified"))
    )
    (net (code "198") (name "Net-(U31-+IND)") (class "Default")
      (node (ref "U31") (pin "12") (pinfunction "+IND_12") (pintype "unspecified"))
      (node (ref "U32") (pin "22") (pinfunction "W2_22") (pintype "unspecified"))
    )
    (net (code "199") (name "Net-(U31--INA)") (class "Default")
      (node (ref "R125") (pin "2") (pinfunction "2_2") (pintype "unspecified"))
      (node (ref "R126") (pin "2") (pinfunction "2_2") (pintype "unspecified"))
      (node (ref "U31") (pin "2") (pinfunction "-INA_2") (pintype "unspecified"))
    )
    (net (code "200") (name "Net-(U31--INB)") (class "Default")
      (node (ref "R127") (pin "1") (pinfunction "1_1") (pintype "unspecified"))
      (node (ref "R128") (pin "2") (pinfunction "2_2") (pintype "unspecified"))
      (node (ref "U31") (pin "6") (pinfunction "-INB_6") (pintype "unspecified"))
    )
    (net (code "201") (name "Net-(U31--INC)") (class "Default")
      (node (ref "R132") (pin "1") (pinfunction "1_1") (pintype "unspecified"))
      (node (ref "R133") (pin "1") (pinfunction "1_1") (pintype "unspecified"))
      (node (ref "U31") (pin "9") (pinfunction "-INC_9") (pintype "unspecified"))
    )
    (net (code "202") (name "Net-(U31--IND)") (class "Default")
      (node (ref "R131") (pin "2") (pinfunction "2_2") (pintype "unspecified"))
      (node (ref "R134") (pin "1") (pinfunction "1_1") (pintype "unspecified"))
      (node (ref "U31") (pin "13") (pinfunction "-IND_13") (pintype "unspecified"))
    )
    (net (code "203") (name "Net-(U31-OUTA)") (class "Default")
      (node (ref "R125") (pin "1") (pinfunction "1_1") (pintype "unspecified"))
      (node (ref "U31") (pin "1") (pinfunction "OUTA_1") (pintype "unspecified"))
      (node (ref "U58") (pin "4") (pinfunction "4_4") (pintype "unspecified"))
    )
    (net (code "204") (name "Net-(U31-OUTB)") (class "Default")
      (node (ref "R127") (pin "2") (pinfunction "2_2") (pintype "unspecified"))
      (node (ref "U31") (pin "7") (pinfunction "OUTB_7") (pintype "unspecified"))
      (node (ref "U58") (pin "2") (pinfunction "2_2") (pintype "unspecified"))
    )
    (net (code "205") (name "Net-(U31-OUTC)") (class "Default")
      (node (ref "R132") (pin "2") (pinfunction "2_2") (pintype "unspecified"))
      (node (ref "U31") (pin "8") (pinfunction "OUTC_8") (pintype "unspecified"))
      (node (ref "U58") (pin "1") (pinfunction "1_1") (pintype "unspecified"))
    )
    (net (code "206") (name "Net-(U31-OUTD)") (class "Default")
      (node (ref "R131") (pin "1") (pinfunction "1_1") (pintype "unspecified"))
      (node (ref "U31") (pin "14") (pinfunction "OUTD_14") (pintype "unspecified"))
      (node (ref "U58") (pin "3") (pinfunction "3_3") (pintype "unspecified"))
    )
    (net (code "207") (name "Net-(U32-SDO{slash}O1)") (class "Default")
      (node (ref "R135") (pin "1") (pinfunction "1_1") (pintype "unspecified"))
      (node (ref "U32") (pin "16") (pinfunction "SDO/O1_16") (pintype "unspecified"))
      (node (ref "U36") (pin "11") (pinfunction "SDI/SDA_11") (pintype "unspecified"))
    )
    (net (code "208") (name "Net-(U33-SDI{slash}SDA)") (class "Default")
      (node (ref "R153") (pin "1") (pinfunction "1_1") (pintype "unspecified"))
      (node (ref "U33") (pin "11") (pinfunction "SDI/SDA_11") (pintype "unspecified"))
      (node (ref "U36") (pin "16") (pinfunction "SDO/O1_16") (pintype "unspecified"))
    )
    (net (code "209") (name "Net-(U33-W1)") (class "Default")
      (node (ref "U33") (pin "3") (pinfunction "W1_3") (pintype "unspecified"))
      (node (ref "U34") (pin "3") (pinfunction "+INA_3") (pintype "unspecified"))
    )
    (net (code "210") (name "Net-(U33-W2)") (class "Default")
      (node (ref "U33") (pin "22") (pinfunction "W2_22") (pintype "unspecified"))
      (node (ref "U34") (pin "12") (pinfunction "+IND_12") (pintype "unspecified"))
    )
    (net (code "211") (name "Net-(U33-W3)") (class "Default")
      (node (ref "U33") (pin "6") (pinfunction "W3_6") (pintype "unspecified"))
      (node (ref "U34") (pin "5") (pinfunction "+INB_5") (pintype "unspecified"))
    )
    (net (code "212") (name "Net-(U33-W4)") (class "Default")
      (node (ref "U33") (pin "19") (pinfunction "W4_19") (pintype "unspecified"))
      (node (ref "U34") (pin "10") (pinfunction "+INC_10") (pintype "unspecified"))
    )
    (net (code "213") (name "Net-(U34--INA)") (class "Default")
      (node (ref "R143") (pin "2") (pinfunction "2_2") (pintype "unspecified"))
      (node (ref "R144") (pin "2") (pinfunction "2_2") (pintype "unspecified"))
      (node (ref "U34") (pin "2") (pinfunction "-INA_2") (pintype "unspecified"))
    )
    (net (code "214") (name "Net-(U34--INB)") (class "Default")
      (node (ref "R141") (pin "2") (pinfunction "2_2") (pintype "unspecified"))
      (node (ref "R142") (pin "1") (pinfunction "1_1") (pintype "unspecified"))
      (node (ref "U34") (pin "6") (pinfunction "-INB_6") (pintype "unspecified"))
    )
    (net (code "215") (name "Net-(U34--INC)") (class "Default")
      (node (ref "R138") (pin "1") (pinfunction "1_1") (pintype "unspecified"))
      (node (ref "R139") (pin "1") (pinfunction "1_1") (pintype "unspecified"))
      (node (ref "U34") (pin "9") (pinfunction "-INC_9") (pintype "unspecified"))
    )
    (net (code "216") (name "Net-(U34--IND)") (class "Default")
      (node (ref "R137") (pin "1") (pinfunction "1_1") (pintype "unspecified"))
      (node (ref "R140") (pin "2") (pinfunction "2_2") (pintype "unspecified"))
      (node (ref "U34") (pin "13") (pinfunction "-IND_13") (pintype "unspecified"))
    )
    (net (code "217") (name "Net-(U34-OUTA)") (class "Default")
      (node (ref "R144") (pin "1") (pinfunction "1_1") (pintype "unspecified"))
      (node (ref "U34") (pin "1") (pinfunction "OUTA_1") (pintype "unspecified"))
      (node (ref "U60") (pin "4") (pinfunction "4_4") (pintype "unspecified"))
    )
    (net (code "218") (name "Net-(U34-OUTB)") (class "Default")
      (node (ref "R142") (pin "2") (pinfunction "2_2") (pintype "unspecified"))
      (node (ref "U34") (pin "7") (pinfunction "OUTB_7") (pintype "unspecified"))
      (node (ref "U60") (pin "2") (pinfunction "2_2") (pintype "unspecified"))
    )
    (net (code "219") (name "Net-(U34-OUTC)") (class "Default")
      (node (ref "R139") (pin "2") (pinfunction "2_2") (pintype "unspecified"))
      (node (ref "U34") (pin "8") (pinfunction "OUTC_8") (pintype "unspecified"))
      (node (ref "U60") (pin "1") (pinfunction "1_1") (pintype "unspecified"))
    )
    (net (code "220") (name "Net-(U34-OUTD)") (class "Default")
      (node (ref "R140") (pin "1") (pinfunction "1_1") (pintype "unspecified"))
      (node (ref "U34") (pin "14") (pinfunction "OUTD_14") (pintype "unspecified"))
      (node (ref "U60") (pin "3") (pinfunction "3_3") (pintype "unspecified"))
    )
    (net (code "221") (name "Net-(U35-+INA)") (class "Default")
      (node (ref "U35") (pin "3") (pinfunction "+INA_3") (pintype "unspecified"))
      (node (ref "U36") (pin "3") (pinfunction "W1_3") (pintype "unspecified"))
    )
    (net (code "222") (name "Net-(U35-+INB)") (class "Default")
      (node (ref "U35") (pin "5") (pinfunction "+INB_5") (pintype "unspecified"))
      (node (ref "U36") (pin "6") (pinfunction "W3_6") (pintype "unspecified"))
    )
    (net (code "223") (name "Net-(U35-+INC)") (class "Default")
      (node (ref "U35") (pin "10") (pinfunction "+INC_10") (pintype "unspecified"))
      (node (ref "U36") (pin "19") (pinfunction "W4_19") (pintype "unspecified"))
    )
    (net (code "224") (name "Net-(U35-+IND)") (class "Default")
      (node (ref "U35") (pin "12") (pinfunction "+IND_12") (pintype "unspecified"))
      (node (ref "U36") (pin "22") (pinfunction "W2_22") (pintype "unspecified"))
    )
    (net (code "225") (name "Net-(U35--INA)") (class "Default")
      (node (ref "R145") (pin "2") (pinfunction "2_2") (pintype "unspecified"))
      (node (ref "R146") (pin "2") (pinfunction "2_2") (pintype "unspecified"))
      (node (ref "U35") (pin "2") (pinfunction "-INA_2") (pintype "unspecified"))
    )
    (net (code "226") (name "Net-(U35--INB)") (class "Default")
      (node (ref "R147") (pin "1") (pinfunction "1_1") (pintype "unspecified"))
      (node (ref "R148") (pin "2") (pinfunction "2_2") (pintype "unspecified"))
      (node (ref "U35") (pin "6") (pinfunction "-INB_6") (pintype "unspecified"))
    )
    (net (code "227") (name "Net-(U35--INC)") (class "Default")
      (node (ref "R150") (pin "1") (pinfunction "1_1") (pintype "unspecified"))
      (node (ref "R151") (pin "1") (pinfunction "1_1") (pintype "unspecified"))
      (node (ref "U35") (pin "9") (pinfunction "-INC_9") (pintype "unspecified"))
    )
    (net (code "228") (name "Net-(U35--IND)") (class "Default")
      (node (ref "R149") (pin "2") (pinfunction "2_2") (pintype "unspecified"))
      (node (ref "R152") (pin "1") (pinfunction "1_1") (pintype "unspecified"))
      (node (ref "U35") (pin "13") (pinfunction "-IND_13") (pintype "unspecified"))
    )
    (net (code "229") (name "Net-(U35-OUTA)") (class "Default")
      (node (ref "R145") (pin "1") (pinfunction "1_1") (pintype "unspecified"))
      (node (ref "U35") (pin "1") (pinfunction "OUTA_1") (pintype "unspecified"))
      (node (ref "U59") (pin "4") (pinfunction "4_4") (pintype "unspecified"))
    )
    (net (code "230") (name "Net-(U35-OUTB)") (class "Default")
      (node (ref "R147") (pin "2") (pinfunction "2_2") (pintype "unspecified"))
      (node (ref "U35") (pin "7") (pinfunction "OUTB_7") (pintype "unspecified"))
      (node (ref "U59") (pin "2") (pinfunction "2_2") (pintype "unspecified"))
    )
    (net (code "231") (name "Net-(U35-OUTC)") (class "Default")
      (node (ref "R150") (pin "2") (pinfunction "2_2") (pintype "unspecified"))
      (node (ref "U35") (pin "8") (pinfunction "OUTC_8") (pintype "unspecified"))
      (node (ref "U59") (pin "1") (pinfunction "1_1") (pintype "unspecified"))
    )
    (net (code "232") (name "Net-(U35-OUTD)") (class "Default")
      (node (ref "R149") (pin "1") (pinfunction "1_1") (pintype "unspecified"))
      (node (ref "U35") (pin "14") (pinfunction "OUTD_14") (pintype "unspecified"))
      (node (ref "U59") (pin "3") (pinfunction "3_3") (pintype "unspecified"))
    )
    (net (code "233") (name "REAL5WAVES") (class "Default")
      (node (ref "R129") (pin "1") (pinfunction "1_1") (pintype "unspecified"))
      (node (ref "R130") (pin "1") (pinfunction "1_1") (pintype "unspecified"))
      (node (ref "U25") (pin "3") (pinfunction "OUT_3") (pintype "unspecified"))
      (node (ref "U40") (pin "3") (pinfunction "3_3") (pintype "unspecified"))
    )
    (net (code "234") (name "REALVOUT_5+") (class "Default")
      (node (ref "C6") (pin "1") (pinfunction "1_1") (pintype "unspecified"))
      (node (ref "C8") (pin "2") (pinfunction "2_2") (pintype "unspecified"))
      (node (ref "U41") (pin "3") (pinfunction "3_3") (pintype "unspecified"))
      (node (ref "U6") (pin "1") (pinfunction "OUTP_1") (pintype "unspecified"))
    )
    (net (code "235") (name "REALVOUT_5-") (class "Default")
      (node (ref "C7") (pin "1") (pinfunction "1_1") (pintype "unspecified"))
      (node (ref "C9") (pin "2") (pinfunction "2_2") (pintype "unspecified"))
      (node (ref "U42") (pin "3") (pinfunction "3_3") (pintype "unspecified"))
      (node (ref "U6") (pin "7") (pinfunction "OUTN_7") (pintype "unspecified"))
    )
    (net (code "236") (name "REALVOUT_12+") (class "Default")
      (node (ref "C4") (pin "1") (pinfunction "1_1") (pintype "unspecified"))
      (node (ref "C5") (pin "1") (pinfunction "1_1") (pintype "unspecified"))
      (node (ref "R10") (pin "1") (pinfunction "1_1") (pintype "unspecified"))
      (node (ref "U4") (pin "A1") (pinfunction "VOUT1P_A1") (pintype "unspecified"))
      (node (ref "U4") (pin "A2") (pinfunction "VOUT1P_A2") (pintype "unspecified"))
      (node (ref "U4") (pin "B1") (pinfunction "VOUT1P_B1") (pintype "unspecified"))
      (node (ref "U4") (pin "B2") (pinfunction "VOUT1P_B2") (pintype "unspecified"))
      (node (ref "U43") (pin "3") (pinfunction "3_3") (pintype "unspecified"))
      (node (ref "U6") (pin "12") (pinfunction "SHDNP#_12") (pintype "unspecified"))
      (node (ref "U6") (pin "14") (pinfunction "INP_14") (pintype "unspecified"))
    )
    (net (code "237") (name "REALVOUT_12-") (class "Default")
      (node (ref "C20") (pin "1") (pinfunction "1_1") (pintype "unspecified"))
      (node (ref "C47") (pin "2") (pinfunction "2_2") (pintype "unspecified"))
      (node (ref "R9") (pin "1") (pinfunction "1_1") (pintype "unspecified"))
      (node (ref "U4") (pin "G1") (pinfunction "VOUT2N_G1") (pintype "unspecified"))
      (node (ref "U4") (pin "G2") (pinfunction "VOUT2N_G2") (pintype "unspecified"))
      (node (ref "U4") (pin "H1") (pinfunction "VOUT2N_H1") (pintype "unspecified"))
      (node (ref "U4") (pin "H2") (pinfunction "VOUT2N_H2") (pintype "unspecified"))
      (node (ref "U4") (pin "J2") (pinfunction "VOUT2N_J2") (pintype "unspecified"))
      (node (ref "U44") (pin "3") (pinfunction "3_3") (pintype "unspecified"))
      (node (ref "U6") (pin "10") (pinfunction "SHDNN#_10") (pintype "unspecified"))
      (node (ref "U6") (pin "16") (pinfunction "INN_16") (pintype "unspecified"))
      (node (ref "U6") (pin "6") (pinfunction "INN_6") (pintype "unspecified"))
      (node (ref "U6") (pin "9") (pinfunction "INN_9") (pintype "unspecified"))
    )
    (net (code "238") (name "VL") (class "Default")
      (node (ref "U1") (pin "10") (pinfunction "VLOGIC_10") (pintype "unspecified"))
      (node (ref "U1") (pin "14") (pinfunction "#RES/AD1_14") (pintype "unspecified"))
      (node (ref "U12") (pin "10") (pinfunction "VLOGIC_10") (pintype "unspecified"))
      (node (ref "U12") (pin "14") (pinfunction "#RES/AD1_14") (pintype "unspecified"))
      (node (ref "U13") (pin "10") (pinfunction "VLOGIC_10") (pintype "unspecified"))
      (node (ref "U13") (pin "14") (pinfunction "#RES/AD1_14") (pintype "unspecified"))
      (node (ref "U17") (pin "10") (pinfunction "VLOGIC_10") (pintype "unspecified"))
      (node (ref "U17") (pin "14") (pinfunction "#RES/AD1_14") (pintype "unspecified"))
      (node (ref "U18") (pin "10") (pinfunction "VLOGIC_10") (pintype "unspecified"))
      (node (ref "U18") (pin "14") (pinfunction "#RES/AD1_14") (pintype "unspecified"))
      (node (ref "U21") (pin "10") (pinfunction "VLOGIC_10") (pintype "unspecified"))
      (node (ref "U21") (pin "14") (pinfunction "#RES/AD1_14") (pintype "unspecified"))
      (node (ref "U22") (pin "10") (pinfunction "VLOGIC_10") (pintype "unspecified"))
      (node (ref "U22") (pin "14") (pinfunction "#RES/AD1_14") (pintype "unspecified"))
      (node (ref "U26") (pin "10") (pinfunction "VLOGIC_10") (pintype "unspecified"))
      (node (ref "U26") (pin "14") (pinfunction "#RES/AD1_14") (pintype "unspecified"))
      (node (ref "U27") (pin "10") (pinfunction "VLOGIC_10") (pintype "unspecified"))
      (node (ref "U27") (pin "14") (pinfunction "#RES/AD1_14") (pintype "unspecified"))
      (node (ref "U3") (pin "10") (pinfunction "VLOGIC_10") (pintype "unspecified"))
      (node (ref "U3") (pin "14") (pinfunction "#RES/AD1_14") (pintype "unspecified"))
      (node (ref "U30") (pin "10") (pinfunction "VLOGIC_10") (pintype "unspecified"))
      (node (ref "U30") (pin "14") (pinfunction "#RES/AD1_14") (pintype "unspecified"))
      (node (ref "U32") (pin "10") (pinfunction "VLOGIC_10") (pintype "unspecified"))
      (node (ref "U32") (pin "14") (pinfunction "#RES/AD1_14") (pintype "unspecified"))
      (node (ref "U33") (pin "10") (pinfunction "VLOGIC_10") (pintype "unspecified"))
      (node (ref "U33") (pin "14") (pinfunction "#RES/AD1_14") (pintype "unspecified"))
      (node (ref "U36") (pin "10") (pinfunction "VLOGIC_10") (pintype "unspecified"))
      (node (ref "U36") (pin "14") (pinfunction "#RES/AD1_14") (pintype "unspecified"))
      (node (ref "U37") (pin "3") (pinfunction "VL_3") (pintype "unspecified"))
      (node (ref "U8") (pin "10") (pinfunction "VLOGIC_10") (pintype "unspecified"))
      (node (ref "U8") (pin "14") (pinfunction "#RES/AD1_14") (pintype "unspecified"))
      (node (ref "U9") (pin "10") (pinfunction "VLOGIC_10") (pintype "unspecified"))
      (node (ref "U9") (pin "14") (pinfunction "#RES/AD1_14") (pintype "unspecified"))
    )
    (net (code "239") (name "VOUT_5+") (class "Default")
      (node (ref "U1") (pin "15") (pinfunction "#SHDN_15") (pintype "unspecified"))
      (node (ref "U1") (pin "7") (pinfunction "VDD_7") (pintype "unspecified"))
      (node (ref "U12") (pin "15") (pinfunction "#SHDN_15") (pintype "unspecified"))
      (node (ref "U12") (pin "7") (pinfunction "VDD_7") (pintype "unspecified"))
      (node (ref "U13") (pin "15") (pinfunction "#SHDN_15") (pintype "unspecified"))
      (node (ref "U13") (pin "7") (pinfunction "VDD_7") (pintype "unspecified"))
      (node (ref "U17") (pin "15") (pinfunction "#SHDN_15") (pintype "unspecified"))
      (node (ref "U17") (pin "7") (pinfunction "VDD_7") (pintype "unspecified"))
      (node (ref "U18") (pin "15") (pinfunction "#SHDN_15") (pintype "unspecified"))
      (node (ref "U18") (pin "7") (pinfunction "VDD_7") (pintype "unspecified"))
      (node (ref "U21") (pin "15") (pinfunction "#SHDN_15") (pintype "unspecified"))
      (node (ref "U21") (pin "7") (pinfunction "VDD_7") (pintype "unspecified"))
      (node (ref "U22") (pin "15") (pinfunction "#SHDN_15") (pintype "unspecified"))
      (node (ref "U22") (pin "7") (pinfunction "VDD_7") (pintype "unspecified"))
      (node (ref "U25") (pin "4") (pinfunction "RESET_4") (pintype "unspecified"))
      (node (ref "U25") (pin "8") (pinfunction "VCC_8") (pintype "unspecified"))
      (node (ref "U26") (pin "15") (pinfunction "#SHDN_15") (pintype "unspecified"))
      (node (ref "U26") (pin "7") (pinfunction "VDD_7") (pintype "unspecified"))
      (node (ref "U27") (pin "15") (pinfunction "#SHDN_15") (pintype "unspecified"))
      (node (ref "U27") (pin "7") (pinfunction "VDD_7") (pintype "unspecified"))
      (node (ref "U3") (pin "15") (pinfunction "#SHDN_15") (pintype "unspecified"))
      (node (ref "U3") (pin "7") (pinfunction "VDD_7") (pintype "unspecified"))
      (node (ref "U30") (pin "15") (pinfunction "#SHDN_15") (pintype "unspecified"))
      (node (ref "U30") (pin "7") (pinfunction "VDD_7") (pintype "unspecified"))
      (node (ref "U32") (pin "15") (pinfunction "#SHDN_15") (pintype "unspecified"))
      (node (ref "U32") (pin "7") (pinfunction "VDD_7") (pintype "unspecified"))
      (node (ref "U33") (pin "15") (pinfunction "#SHDN_15") (pintype "unspecified"))
      (node (ref "U33") (pin "7") (pinfunction "VDD_7") (pintype "unspecified"))
      (node (ref "U36") (pin "15") (pinfunction "#SHDN_15") (pintype "unspecified"))
      (node (ref "U36") (pin "7") (pinfunction "VDD_7") (pintype "unspecified"))
      (node (ref "U41") (pin "2") (pinfunction "2_2") (pintype "unspecified"))
      (node (ref "U8") (pin "15") (pinfunction "#SHDN_15") (pintype "unspecified"))
      (node (ref "U8") (pin "7") (pinfunction "VDD_7") (pintype "unspecified"))
      (node (ref "U9") (pin "15") (pinfunction "#SHDN_15") (pintype "unspecified"))
      (node (ref "U9") (pin "7") (pinfunction "VDD_7") (pintype "unspecified"))
    )
    (net (code "240") (name "VOUT_5-") (class "Default")
      (node (ref "C1") (pin "2") (pinfunction "2_2") (pintype "unspecified"))
      (node (ref "C2") (pin "2") (pinfunction "2_2") (pintype "unspecified"))
      (node (ref "U1") (pin "18") (pinfunction "VSS_18") (pintype "unspecified"))
      (node (ref "U12") (pin "18") (pinfunction "VSS_18") (pintype "unspecified"))
      (node (ref "U13") (pin "18") (pinfunction "VSS_18") (pintype "unspecified"))
      (node (ref "U17") (pin "18") (pinfunction "VSS_18") (pintype "unspecified"))
      (node (ref "U18") (pin "18") (pinfunction "VSS_18") (pintype "unspecified"))
      (node (ref "U21") (pin "18") (pinfunction "VSS_18") (pintype "unspecified"))
      (node (ref "U22") (pin "18") (pinfunction "VSS_18") (pintype "unspecified"))
      (node (ref "U25") (pin "1") (pinfunction "GND_1") (pintype "unspecified"))
      (node (ref "U26") (pin "18") (pinfunction "VSS_18") (pintype "unspecified"))
      (node (ref "U27") (pin "18") (pinfunction "VSS_18") (pintype "unspecified"))
      (node (ref "U3") (pin "18") (pinfunction "VSS_18") (pintype "unspecified"))
      (node (ref "U30") (pin "18") (pinfunction "VSS_18") (pintype "unspecified"))
      (node (ref "U32") (pin "18") (pinfunction "VSS_18") (pintype "unspecified"))
      (node (ref "U33") (pin "18") (pinfunction "VSS_18") (pintype "unspecified"))
      (node (ref "U36") (pin "18") (pinfunction "VSS_18") (pintype "unspecified"))
      (node (ref "U42") (pin "2") (pinfunction "2_2") (pintype "unspecified"))
      (node (ref "U8") (pin "18") (pinfunction "VSS_18") (pintype "unspecified"))
      (node (ref "U9") (pin "18") (pinfunction "VSS_18") (pintype "unspecified"))
    )
    (net (code "241") (name "VOUT_12+") (class "Default")
      (node (ref "U10") (pin "4") (pinfunction "V+_4") (pintype "unspecified"))
      (node (ref "U11") (pin "4") (pinfunction "V+_4") (pintype "unspecified"))
      (node (ref "U14") (pin "4") (pinfunction "V+_4") (pintype "unspecified"))
      (node (ref "U16") (pin "4") (pinfunction "V+_4") (pintype "unspecified"))
      (node (ref "U19") (pin "4") (pinfunction "V+_4") (pintype "unspecified"))
      (node (ref "U2") (pin "4") (pinfunction "V+_4") (pintype "unspecified"))
      (node (ref "U20") (pin "4") (pinfunction "V+_4") (pintype "unspecified"))
      (node (ref "U23") (pin "4") (pinfunction "V+_4") (pintype "unspecified"))
      (node (ref "U24") (pin "4") (pinfunction "V+_4") (pintype "unspecified"))
      (node (ref "U28") (pin "4") (pinfunction "V+_4") (pintype "unspecified"))
      (node (ref "U29") (pin "4") (pinfunction "V+_4") (pintype "unspecified"))
      (node (ref "U31") (pin "4") (pinfunction "V+_4") (pintype "unspecified"))
      (node (ref "U34") (pin "4") (pinfunction "V+_4") (pintype "unspecified"))
      (node (ref "U35") (pin "4") (pinfunction "V+_4") (pintype "unspecified"))
      (node (ref "U43") (pin "2") (pinfunction "2_2") (pintype "unspecified"))
      (node (ref "U5") (pin "4") (pinfunction "V+_4") (pintype "unspecified"))
      (node (ref "U7") (pin "4") (pinfunction "V+_4") (pintype "unspecified"))
    )
    (net (code "242") (name "VOUT_12-") (class "Default")
      (node (ref "U10") (pin "11") (pinfunction "V-_11") (pintype "unspecified"))
      (node (ref "U11") (pin "11") (pinfunction "V-_11") (pintype "unspecified"))
      (node (ref "U14") (pin "11") (pinfunction "V-_11") (pintype "unspecified"))
      (node (ref "U16") (pin "11") (pinfunction "V-_11") (pintype "unspecified"))
      (node (ref "U19") (pin "11") (pinfunction "V-_11") (pintype "unspecified"))
      (node (ref "U2") (pin "11") (pinfunction "V-_11") (pintype "unspecified"))
      (node (ref "U20") (pin "11") (pinfunction "V-_11") (pintype "unspecified"))
      (node (ref "U23") (pin "11") (pinfunction "V-_11") (pintype "unspecified"))
      (node (ref "U24") (pin "11") (pinfunction "V-_11") (pintype "unspecified"))
      (node (ref "U28") (pin "11") (pinfunction "V-_11") (pintype "unspecified"))
      (node (ref "U29") (pin "11") (pinfunction "V-_11") (pintype "unspecified"))
      (node (ref "U31") (pin "11") (pinfunction "V-_11") (pintype "unspecified"))
      (node (ref "U34") (pin "11") (pinfunction "V-_11") (pintype "unspecified"))
      (node (ref "U35") (pin "11") (pinfunction "V-_11") (pintype "unspecified"))
      (node (ref "U44") (pin "2") (pinfunction "2_2") (pintype "unspecified"))
      (node (ref "U5") (pin "11") (pinfunction "V-_11") (pintype "unspecified"))
      (node (ref "U7") (pin "11") (pinfunction "V-_11") (pintype "unspecified"))
    )
    (net (code "243") (name "V_IN_EXT") (class "Default")
      (node (ref "C10") (pin "2") (pinfunction "2_2") (pintype "unspecified"))
      (node (ref "C17") (pin "1") (pinfunction "1_1") (pintype "unspecified"))
      (node (ref "C18") (pin "1") (pinfunction "1_1") (pintype "unspecified"))
      (node (ref "C50") (pin "2") (pinfunction "2_2") (pintype "unspecified"))
      (node (ref "C51") (pin "2") (pinfunction "2_2") (pintype "unspecified"))
      (node (ref "CN1") (pin "1") (pinfunction "1_1") (pintype "unspecified"))
      (node (ref "CN1") (pin "2") (pinfunction "2_2") (pintype "unspecified"))
      (node (ref "CN1") (pin "3") (pinfunction "3_3") (pintype "unspecified"))
      (node (ref "CN1") (pin "4") (pinfunction "4_4") (pintype "unspecified"))
      (node (ref "R27") (pin "1") (pinfunction "1_1") (pintype "unspecified"))
      (node (ref "R28") (pin "2") (pinfunction "2_2") (pintype "unspecified"))
      (node (ref "U38") (pin "1") (pinfunction "VIN_1") (pintype "unspecified"))
      (node (ref "U4") (pin "A5") (pinfunction "VIN1_A5") (pintype "unspecified"))
      (node (ref "U4") (pin "A6") (pinfunction "VIN1_A6") (pintype "unspecified"))
      (node (ref "U4") (pin "A7") (pinfunction "VIN1_A7") (pintype "unspecified"))
      (node (ref "U4") (pin "B7") (pinfunction "RUN1_B7") (pintype "unspecified"))
      (node (ref "U4") (pin "K7") (pinfunction "RUN2_K7") (pintype "unspecified"))
      (node (ref "U4") (pin "L5") (pinfunction "VIN2_L5") (pintype "unspecified"))
      (node (ref "U4") (pin "L6") (pinfunction "VIN2_L6") (pintype "unspecified"))
      (node (ref "U4") (pin "L7") (pinfunction "VIN2_L7") (pintype "unspecified"))
    )
    (net (code "244") (name "unconnected-(U1-NC{slash}O2-Pad17)") (class "Default")
      (node (ref "U1") (pin "17") (pinfunction "NC/O2_17") (pintype "unspecified+no_connect"))
    )
    (net (code "245") (name "unconnected-(U3-NC{slash}O2-Pad17)") (class "Default")
      (node (ref "U3") (pin "17") (pinfunction "NC/O2_17") (pintype "unspecified+no_connect"))
    )
    (net (code "246") (name "unconnected-(U4-CLKOUT2-PadG6)") (class "Default")
      (node (ref "U4") (pin "G6") (pinfunction "CLKOUT2_G6") (pintype "unspecified+no_connect"))
    )
    (net (code "247") (name "unconnected-(U4-SHARE1-PadF3)") (class "Default")
      (node (ref "U4") (pin "F3") (pinfunction "SHARE1_F3") (pintype "unspecified+no_connect"))
    )
    (net (code "248") (name "unconnected-(U4-SHARE2-PadF4)") (class "Default")
      (node (ref "U4") (pin "F4") (pinfunction "SHARE2_F4") (pintype "unspecified+no_connect"))
    )
    (net (code "249") (name "unconnected-(U6-ADJN{slash}NC††-Pad8)") (class "Default")
      (node (ref "U6") (pin "8") (pinfunction "ADJN/NC††_8") (pintype "unspecified+no_connect"))
    )
    (net (code "250") (name "unconnected-(U6-NC-Pad13)") (class "Default")
      (node (ref "U6") (pin "13") (pinfunction "NC_13") (pintype "unspecified+no_connect"))
    )
    (net (code "251") (name "unconnected-(U6-NC†{slash}ADJP-Pad2)") (class "Default")
      (node (ref "U6") (pin "2") (pinfunction "NC†/ADJP_2") (pintype "unspecified+no_connect"))
    )
    (net (code "252") (name "unconnected-(U8-NC{slash}O2-Pad17)") (class "Default")
      (node (ref "U8") (pin "17") (pinfunction "NC/O2_17") (pintype "unspecified+no_connect"))
    )
    (net (code "253") (name "unconnected-(U9-NC{slash}O2-Pad17)") (class "Default")
      (node (ref "U9") (pin "17") (pinfunction "NC/O2_17") (pintype "unspecified+no_connect"))
    )
    (net (code "254") (name "unconnected-(U12-NC{slash}O2-Pad17)") (class "Default")
      (node (ref "U12") (pin "17") (pinfunction "NC/O2_17") (pintype "unspecified+no_connect"))
    )
    (net (code "255") (name "unconnected-(U13-NC{slash}O2-Pad17)") (class "Default")
      (node (ref "U13") (pin "17") (pinfunction "NC/O2_17") (pintype "unspecified+no_connect"))
    )
    (net (code "256") (name "unconnected-(U17-NC{slash}O2-Pad17)") (class "Default")
      (node (ref "U17") (pin "17") (pinfunction "NC/O2_17") (pintype "unspecified+no_connect"))
    )
    (net (code "257") (name "unconnected-(U18-NC{slash}O2-Pad17)") (class "Default")
      (node (ref "U18") (pin "17") (pinfunction "NC/O2_17") (pintype "unspecified+no_connect"))
    )
    (net (code "258") (name "unconnected-(U21-NC{slash}O2-Pad17)") (class "Default")
      (node (ref "U21") (pin "17") (pinfunction "NC/O2_17") (pintype "unspecified+no_connect"))
    )
    (net (code "259") (name "unconnected-(U22-NC{slash}O2-Pad17)") (class "Default")
      (node (ref "U22") (pin "17") (pinfunction "NC/O2_17") (pintype "unspecified+no_connect"))
    )
    (net (code "260") (name "unconnected-(U26-NC{slash}O2-Pad17)") (class "Default")
      (node (ref "U26") (pin "17") (pinfunction "NC/O2_17") (pintype "unspecified+no_connect"))
    )
    (net (code "261") (name "unconnected-(U27-NC{slash}O2-Pad17)") (class "Default")
      (node (ref "U27") (pin "17") (pinfunction "NC/O2_17") (pintype "unspecified+no_connect"))
    )
    (net (code "262") (name "unconnected-(U30-NC{slash}O2-Pad17)") (class "Default")
      (node (ref "U30") (pin "17") (pinfunction "NC/O2_17") (pintype "unspecified+no_connect"))
    )
    (net (code "263") (name "unconnected-(U32-NC{slash}O2-Pad17)") (class "Default")
      (node (ref "U32") (pin "17") (pinfunction "NC/O2_17") (pintype "unspecified+no_connect"))
    )
    (net (code "264") (name "unconnected-(U33-NC{slash}O2-Pad17)") (class "Default")
      (node (ref "U33") (pin "17") (pinfunction "NC/O2_17") (pintype "unspecified+no_connect"))
    )
    (net (code "265") (name "unconnected-(U36-NC{slash}O2-Pad17)") (class "Default")
      (node (ref "U36") (pin "17") (pinfunction "NC/O2_17") (pintype "unspecified+no_connect"))
    )
  )
)
